# Copy_of_WX0_011_781DL.net
KiCad netlist of a schematic drawn in Altium Designer
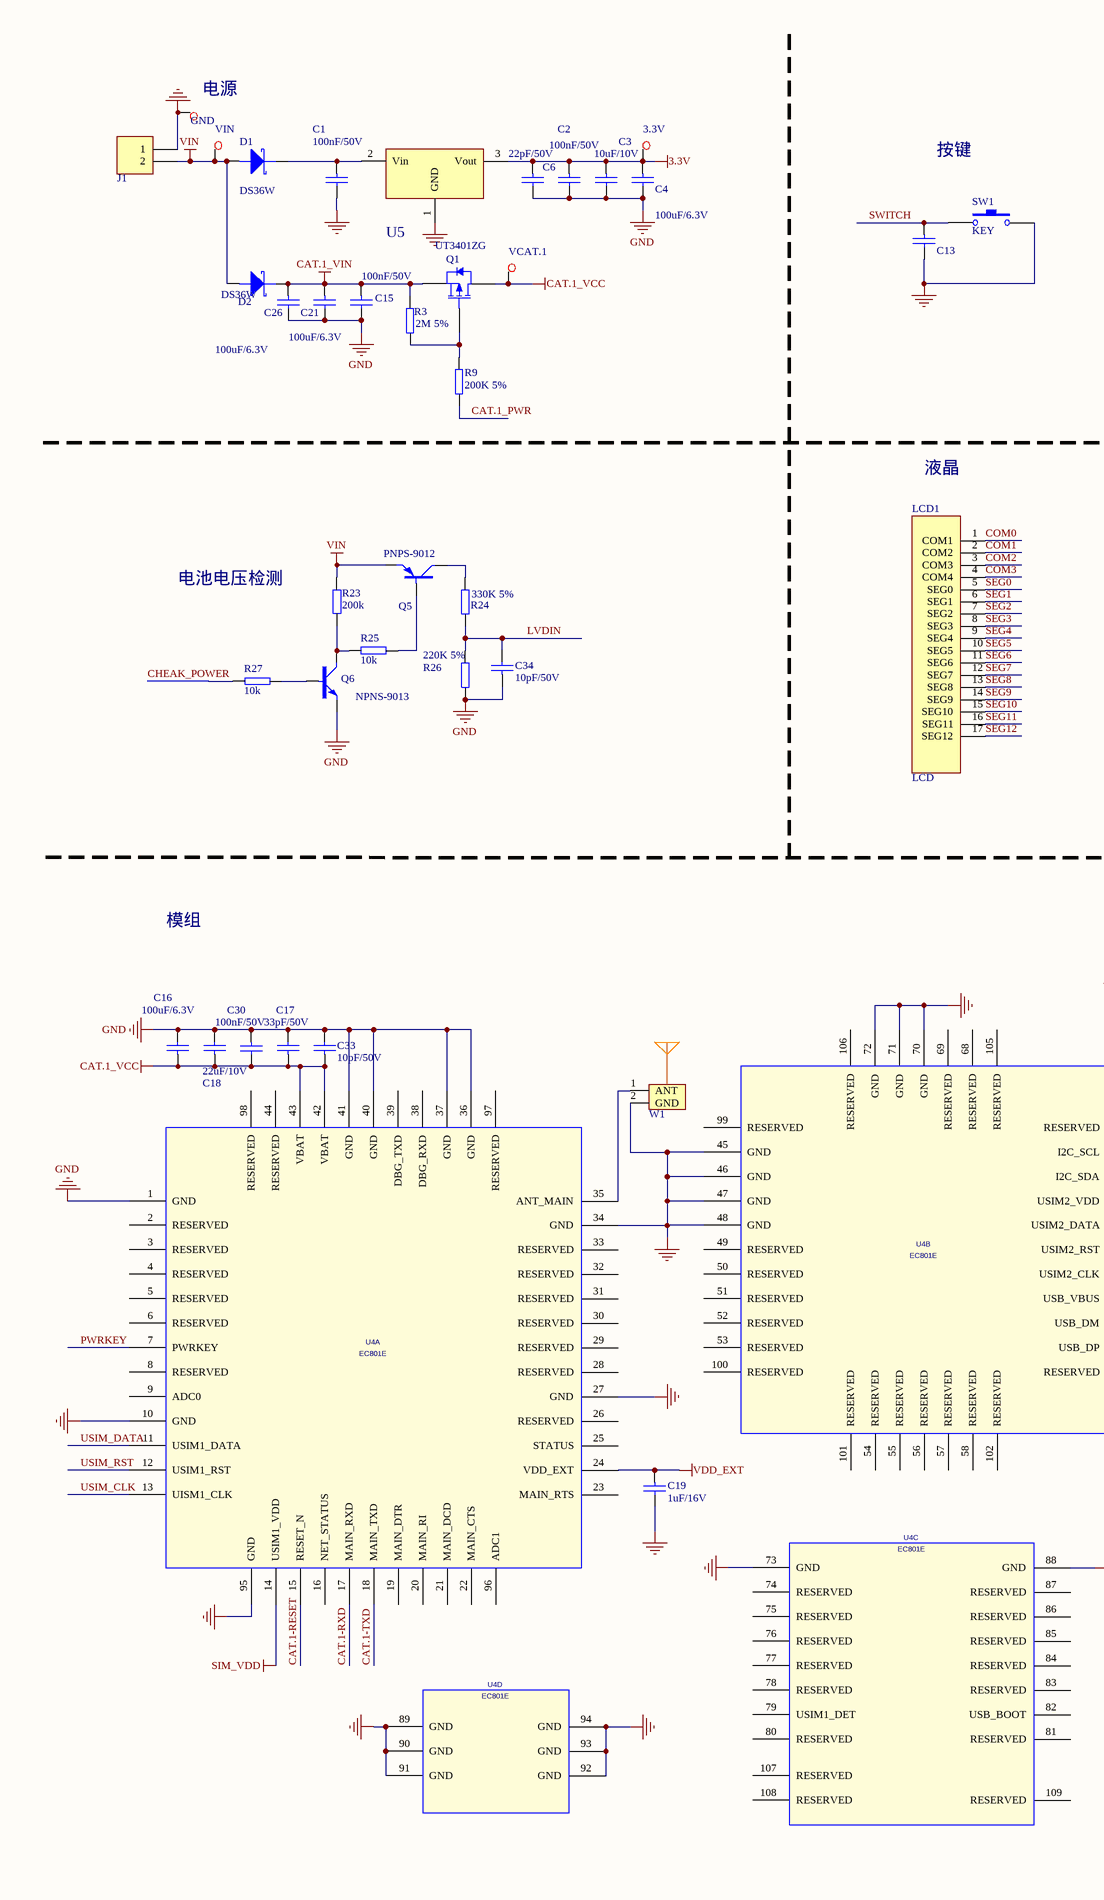
[diagram p0: Copy+of+WX0.011.781DL.schdoc, left]
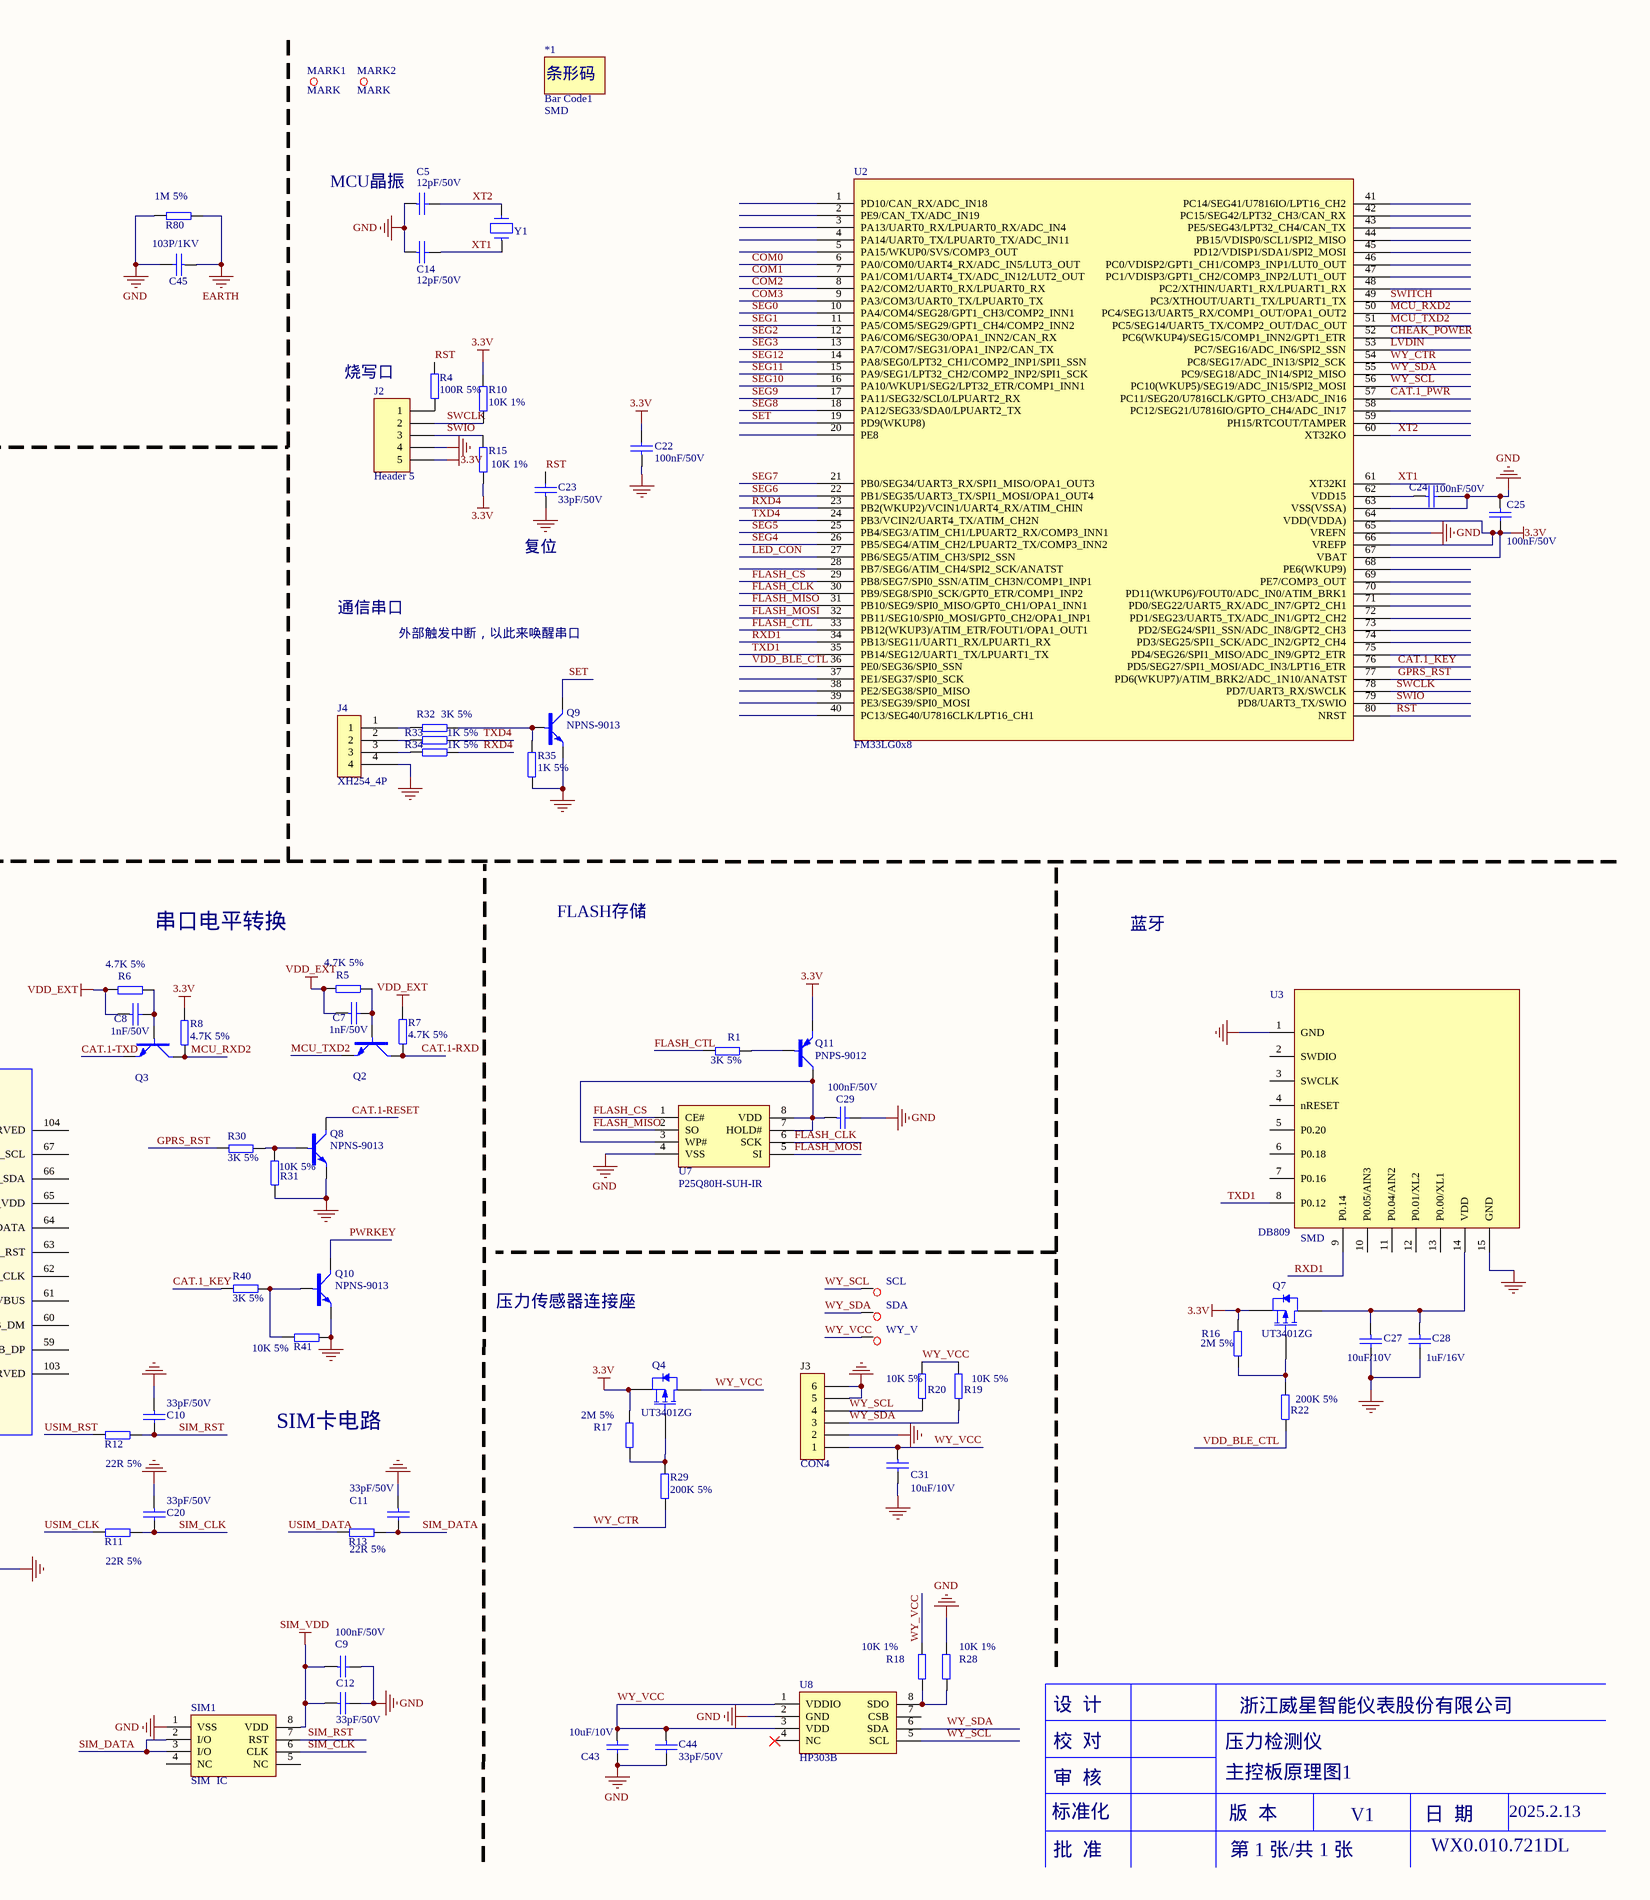
[diagram p1: Copy+of+WX0.011.781DL.schdoc, right]

(export (version "E")
  (design (tool "Eeschema 10.0.6"))
  (components
    (comp (ref "*1")
      (value "Bar Code1")
      (footprint "Bar Code1")
      (description "条形码 ,填充，无需焊接器件")
      (fields (field (name "PART NUMBER") "AD_WXHJ_Bar Code_02") (field (name "SMD/DIP") "SMD"))
      (libsource (lib "Database_Libs2") (part "05_AD_WXHJ_Bar Code_02"))
    )
    (comp (ref "3.3V")
      (value "TEST-PAD")
      (footprint "TEST-PAD")
      (description "单面焊盘测试点")
      (fields (field (name "PART NUMBER") "AD_WXHJ_TEST-PAD_01"))
      (libsource (lib "Database_Libs2") (part "TEST-PAD"))
    )
    (comp (ref "C1")
      (value "100nF/50V")
      (footprint "CAP0603")
      (description "104pF,50 V,±10%,0603,国巨,CC0603KRX7R9BB104")
      (fields (field (name "PART NUMBER") "101020103-0021"))
      (libsource (lib "Database_Libs2") (part "CC03K7R9_100N"))
    )
    (comp (ref "C2")
      (value "100nF/50V")
      (footprint "CAP0603")
      (description "104pF,50 V,±10%,0603,国巨,CC0603KRX7R9BB104")
      (fields (field (name "PART NUMBER") "101020103-0021"))
      (libsource (lib "Database_Libs2") (part "CC03K7R9_100N"))
    )
    (comp (ref "C3")
      (value "10uF/10V")
      (footprint "CAP0603")
      (description "106pF,10 V,±10%,0603,村田,GRM188R61A106KE47D")
      (fields (field (name "PART NUMBER") "101020103-0026"))
      (libsource (lib "Database_Libs2") (part "CC03K5R6_10U"))
    )
    (comp (ref "C4")
      (value "100uF/6.3V")
      (footprint "GRM1206")
      (description "100uF,6.3 V,±20%,1206,村田,GRM31CR60J107ME39L")
      (fields (field (name "PART NUMBER") "101020101-0020"))
      (libsource (lib "Database_Libs2") (part "CC06M5R5_107P"))
    )
    (comp (ref "C5")
      (value "12pF/50V")
      (footprint "CAP0603")
      (description "12P,50 V,±5%,0603,国巨,CC0603JRNPO9BN12")
      (fields (field (name "PART NUMBER") "101020103-0005"))
      (libsource (lib "Database_Libs2") (part "CC03JPO9_12P"))
    )
    (comp (ref "C6")
      (value "22pF/50V")
      (footprint "CAP0603")
      (description "22pF,50 V,±5%,0603,国巨,CC0603JRNPO9BN22")
      (fields (field (name "PART NUMBER") "101020103-0009"))
      (libsource (lib "Database_Libs2") (part "CC03JPO9_22P"))
    )
    (comp (ref "C7")
      (value "1nF/50V")
      (footprint "CAP0603")
      (description "102pF,50 V,±10%,0603,国巨,CC0603KRX7R9BB102")
      (fields (field (name "PART NUMBER") "101020103-0022"))
      (libsource (lib "Database_Libs1") (part "CC03K7R9_1N"))
    )
    (comp (ref "C8")
      (value "1nF/50V")
      (footprint "CAP0603")
      (description "102pF,50 V,±10%,0603,国巨,CC0603KRX7R9BB102")
      (fields (field (name "PART NUMBER") "101020103-0022"))
      (libsource (lib "Database_Libs1") (part "CC03K7R9_1N"))
    )
    (comp (ref "C9")
      (value "100nF/50V")
      (footprint "CAP0603")
      (description "104pF,50 V,±10%,0603,国巨,CC0603KRX7R9BB104")
      (fields (field (name "PART NUMBER") "101020103-0021"))
      (libsource (lib "Database_Libs2") (part "CC03K7R9_100N"))
    )
    (comp (ref "C10")
      (value "33pF/50V")
      (footprint "CAP0603")
      (description "33pF,50 V,±10%,0603,国巨,CC0603KRNPO9BN33")
      (fields (field (name "PART NUMBER") "101020103-0027"))
      (libsource (lib "Database_Libs2") (part "CC03KPO9_33P"))
    )
    (comp (ref "C11")
      (value "33pF/50V")
      (footprint "CAP0603")
      (description "33pF,50 V,±10%,0603,国巨,CC0603KRNPO9BN33")
      (fields (field (name "PART NUMBER") "101020103-0027"))
      (libsource (lib "Database_Libs2") (part "CC03KPO9_33P"))
    )
    (comp (ref "C12")
      (value "33pF/50V")
      (footprint "CAP0603")
      (description "33pF,50 V,±10%,0603,国巨,CC0603KRNPO9BN33")
      (fields (field (name "PART NUMBER") "101020103-0027"))
      (libsource (lib "Database_Libs2") (part "CC03KPO9_33P"))
    )
    (comp (ref "C13")
      (value "100nF/50V")
      (footprint "CAP0603")
      (description "104pF,50 V,±10%,0603,国巨,CC0603KRX7R9BB104")
      (fields (field (name "PART NUMBER") "101020103-0021"))
      (libsource (lib "Database_Libs2") (part "CC03K7R9_100N"))
    )
    (comp (ref "C14")
      (value "12pF/50V")
      (footprint "CAP0603")
      (description "12P,50 V,±5%,0603,国巨,CC0603JRNPO9BN12")
      (fields (field (name "PART NUMBER") "101020103-0005"))
      (libsource (lib "Database_Libs2") (part "CC03JPO9_12P"))
    )
    (comp (ref "C15")
      (value "100nF/50V")
      (footprint "CAP0603")
      (description "104pF,50 V,±10%,0603,国巨,CC0603KRX7R9BB104")
      (fields (field (name "PART NUMBER") "101020103-0021"))
      (libsource (lib "Database_Libs2") (part "CC03K7R9_100N"))
    )
    (comp (ref "C16")
      (value "100uF/6.3V")
      (footprint "GRM1206")
      (description "100uF,6.3 V,±20%,1206,村田,GRM31CR60J107ME39L")
      (fields (field (name "PART NUMBER") "101020101-0020"))
      (libsource (lib "Database_Libs2") (part "CC06M5R5_107P"))
    )
    (comp (ref "C17")
      (value "33pF/50V")
      (footprint "CAP0603")
      (description "33pF,50 V,±10%,0603,国巨,CC0603KRNPO9BN33")
      (fields (field (name "PART NUMBER") "101020103-0027"))
      (libsource (lib "Database_Libs2") (part "CC03KPO9_33P"))
    )
    (comp (ref "C18")
      (value "22uF/10V")
      (footprint "CAP0805")
      (description "226P,10 V,±20%,0805,村田电子有限公司,GRM21BR61A226ME51L")
      (fields (field (name "PART NUMBER") "101020102-0012"))
      (libsource (lib "Database_Libs2") (part "CC05M5R6_226P"))
    )
    (comp (ref "C19")
      (value "1uF/16V")
      (footprint "CAP0603")
      (description "105pF,16 V,±10%,0603,国巨,CC0603KRX7R7BB105")
      (fields (field (name "PART NUMBER") "101020103-0003"))
      (libsource (lib "Database_Libs1") (part "CC03K7R7_1U"))
    )
    (comp (ref "C20")
      (value "33pF/50V")
      (footprint "CAP0603")
      (description "33pF,50 V,±10%,0603,国巨,CC0603KRNPO9BN33")
      (fields (field (name "PART NUMBER") "101020103-0027"))
      (libsource (lib "Database_Libs2") (part "CC03KPO9_33P"))
    )
    (comp (ref "C21")
      (value "100uF/6.3V")
      (footprint "GRM1206")
      (description "100uF,6.3 V,±20%,1206,村田,GRM31CR60J107ME39L")
      (fields (field (name "PART NUMBER") "101020101-0020"))
      (libsource (lib "Database_Libs2") (part "CC06M5R5_107P"))
    )
    (comp (ref "C22")
      (value "100nF/50V")
      (footprint "CAP0603")
      (description "104pF,50 V,±10%,0603,国巨,CC0603KRX7R9BB104")
      (fields (field (name "PART NUMBER") "101020103-0021"))
      (libsource (lib "Database_Libs2") (part "CC03K7R9_100N"))
    )
    (comp (ref "C23")
      (value "33pF/50V")
      (footprint "CAP0603")
      (description "33pF,50 V,±10%,0603,国巨,CC0603KRNPO9BN33")
      (fields (field (name "PART NUMBER") "101020103-0027"))
      (libsource (lib "Database_Libs2") (part "CC03KPO9_33P"))
    )
    (comp (ref "C24")
      (value "100nF/50V")
      (footprint "CAP0603")
      (description "104pF,50 V,±10%,0603,国巨,CC0603KRX7R9BB104")
      (fields (field (name "PART NUMBER") "101020103-0021"))
      (libsource (lib "Database_Libs2") (part "CC03K7R9_100N"))
    )
    (comp (ref "C25")
      (value "100nF/50V")
      (footprint "CAP0603")
      (description "104pF,50 V,±10%,0603,国巨,CC0603KRX7R9BB104")
      (fields (field (name "PART NUMBER") "101020103-0021"))
      (libsource (lib "Database_Libs2") (part "CC03K7R9_100N"))
    )
    (comp (ref "C26")
      (value "100uF/6.3V")
      (footprint "GRM1206")
      (description "100uF,6.3 V,±20%,1206,村田,GRM31CR60J107ME39L")
      (fields (field (name "PART NUMBER") "101020101-0020"))
      (libsource (lib "Database_Libs2") (part "CC06M5R5_107P"))
    )
    (comp (ref "C27")
      (value "10uF/10V")
      (footprint "CAP0603")
      (description "106pF,10 V,±10%,0603,村田,GRM188R61A106KE47D")
      (fields (field (name "PART NUMBER") "101020103-0026"))
      (libsource (lib "Database_Libs2") (part "CC03K5R6_10U"))
    )
    (comp (ref "C28")
      (value "1uF/16V")
      (footprint "CAP0603")
      (description "105pF,16 V,±10%,0603,国巨,CC0603KRX7R7BB105")
      (fields (field (name "PART NUMBER") "101020103-0003"))
      (libsource (lib "Database_Libs2") (part "CC03K7R7_1U"))
    )
    (comp (ref "C29")
      (value "100nF/50V")
      (footprint "CAP0603")
      (description "104pF,50 V,±10%,0603,国巨,CC0603KRX7R9BB104")
      (fields (field (name "PART NUMBER") "101020103-0021"))
      (libsource (lib "Database_Libs2") (part "CC03K7R9_100N"))
    )
    (comp (ref "C30")
      (value "100nF/50V")
      (footprint "CAP0603")
      (description "104pF,50 V,±10%,0603,国巨,CC0603KRX7R9BB104")
      (fields (field (name "PART NUMBER") "101020103-0021"))
      (libsource (lib "Database_Libs2") (part "CC03K7R9_100N"))
    )
    (comp (ref "C31")
      (value "10uF/10V")
      (footprint "CAP0603")
      (description "106pF,10 V,±10%,0603,村田,GRM188R61A106KE47D")
      (fields (field (name "PART NUMBER") "101020103-0026"))
      (libsource (lib "Database_Libs2") (part "CC03K5R6_10U"))
    )
    (comp (ref "C33")
      (value "10pF/50V")
      (footprint "CAP0603")
      (description "10pF,50 V,±5%,0603,X7R,国巨,CC0603JRNPO9BN100")
      (fields (field (name "PART NUMBER") "101020103-0014"))
      (libsource (lib "Database_Libs2") (part "CC03JPO9_10P"))
    )
    (comp (ref "C34")
      (value "10pF/50V")
      (footprint "CAP0603")
      (description "10pF,50 V,±5%,0603,X7R,国巨,CC0603JRNPO9BN100")
      (fields (field (name "PART NUMBER") "101020103-0014"))
      (libsource (lib "Database_Libs2") (part "CC03JPO9_10P"))
    )
    (comp (ref "C43")
      (value "10uF/10V")
      (footprint "CAP0603")
      (description "106pF,10 V,±10%,0603,村田,GRM188R61A106KE47D")
      (fields (field (name "PART NUMBER") "101020103-0026"))
      (libsource (lib "Database_Libs2") (part "CC03K5R6_10U"))
    )
    (comp (ref "C44")
      (value "33pF/50V")
      (footprint "CAP0603")
      (description "33pF,50 V,±10%,0603,国巨,CC0603KRNPO9BN33")
      (fields (field (name "PART NUMBER") "101020103-0027"))
      (libsource (lib "Database_Libs2") (part "CC03KPO9_33P"))
    )
    (comp (ref "C45")
      (value "103P/1KV")
      (footprint "CAP1206")
      (description "103P/1KV,±10％,1206")
      (fields (field (name "PART NUMBER") "101020101-0003"))
      (libsource (lib "altium-import") (part "root_3_CC03K7R9_100N_"))
    )
    (comp (ref "D1")
      (value "DS36W")
      (footprint "SOD-123FL")
      (description "DS36W,SOD123-FL,3 A,42 V,60 V,浙江领晨科技有限公司,DS36W")
      (fields (field (name "PART NUMBER") "101040101-0055"))
      (libsource (lib "Database_Libs2") (part "02_DS36W"))
    )
    (comp (ref "D2")
      (value "DS36W")
      (footprint "SOD-123FL")
      (description "DS36W,SOD123-FL,3 A,42 V,60 V,浙江领晨科技有限公司,DS36W")
      (fields (field (name "PART NUMBER") "101040101-0055"))
      (libsource (lib "Database_Libs2") (part "02_DS36W"))
    )
    (comp (ref "GND")
      (value "TEST-PAD")
      (footprint "TEST-PAD")
      (description "单面焊盘测试点")
      (fields (field (name "PART NUMBER") "AD_WXHJ_TEST-PAD_01"))
      (libsource (lib "Database_Libs2") (part "TEST-PAD"))
    )
    (comp (ref "J1")
      (value "Header 2")
      (footprint "VBAT")
      (description "Header, 2-Pin")
      (libsource (lib "CBB_Lib_SCH") (part "Header 2"))
    )
    (comp (ref "J2")
      (value "Header 5")
      (footprint "PIN254_1*5SR")
      (description "Header, 5-Pin")
      (libsource (lib "CBB_Lib_SCH") (part "Header 5"))
    )
    (comp (ref "J3")
      (value "CON4")
      (footprint "WX-PH-4AB")
      (description "Connector")
      (libsource (lib "压力") (part "CON4"))
    )
    (comp (ref "J4")
      (value "XH254_4P")
      (footprint "HDR1X4_2.54")
      (description "单排插针，4PIN,间距2.54mm")
      (fields (field (name "PART NUMBER") "90003"))
      (libsource (lib "Database_Libs1") (part "XH254_4P"))
    )
    (comp (ref "LCD1") (value "LCD") (footprint "JR-H25903AFP") (libsource (lib "压力检测仪") (part "LCDSH")))
    (comp (ref "MARK1")
      (value "MARK")
      (footprint "MARK")
      (description "MARK点")
      (fields (field (name "PART NUMBER") "AD_WXHJ_MARK_01"))
      (libsource (lib "Database_Libs2") (part "MARK"))
    )
    (comp (ref "MARK2")
      (value "MARK")
      (footprint "MARK")
      (description "MARK点")
      (fields (field (name "PART NUMBER") "AD_WXHJ_MARK_01"))
      (libsource (lib "Database_Libs2") (part "MARK"))
    )
    (comp (ref "Q1")
      (value "UT3401ZG")
      (footprint "SOT-23")
      (description "UT3401ZG,P-MOS,SOT-23,UTC,UT3401ZG")
      (fields (field (name "PART NUMBER") "101040201-0013"))
      (libsource (lib "Database_Libs2") (part "03_P-UT3401ZG"))
    )
    (comp (ref "Q2")
      (value "NPNS-9013")
      (footprint "SOT-23")
      (description "9013,NPN,SOT-23,长电,S9013")
      (fields (field (name "PART NUMBER") "101040201-0002"))
      (libsource (lib "Database_Libs2") (part "03_NPNS-9013"))
    )
    (comp (ref "Q3")
      (value "NPNS-9013")
      (footprint "SOT-23")
      (description "9013,NPN,SOT-23,长电,S9013")
      (fields (field (name "PART NUMBER") "101040201-0002"))
      (libsource (lib "Database_Libs2") (part "03_NPNS-9013"))
    )
    (comp (ref "Q4")
      (value "UT3401ZG")
      (footprint "SOT-23")
      (description "UT3401ZG,P-MOS,SOT-23,UTC,UT3401ZG")
      (fields (field (name "PART NUMBER") "101040201-0013"))
      (libsource (lib "Database_Libs2") (part "03_P-UT3401ZG"))
    )
    (comp (ref "Q5")
      (value "PNPS-9012")
      (footprint "SOT-23")
      (description "9012,PNP,SOT-23,JCET;长电,S9012")
      (fields (field (name "PART NUMBER") "101040201-0001"))
      (libsource (lib "Database_Libs2") (part "03_PNPS-9012"))
    )
    (comp (ref "Q6")
      (value "NPNS-9013")
      (footprint "SOT-23")
      (description "9013,NPN,SOT-23,长电,S9013")
      (fields (field (name "PART NUMBER") "101040201-0002"))
      (libsource (lib "Database_Libs2") (part "03_NPNS-9013"))
    )
    (comp (ref "Q7")
      (value "UT3401ZG")
      (footprint "SOT-23")
      (description "UT3401ZG,P-MOS,SOT-23,UTC,UT3401ZG")
      (fields (field (name "PART NUMBER") "101040201-0013"))
      (libsource (lib "Database_Libs2") (part "03_P-UT3401ZG"))
    )
    (comp (ref "Q8")
      (value "NPNS-9013")
      (footprint "SOT-23")
      (description "9013,NPN,SOT-23,长电,S9013")
      (fields (field (name "PART NUMBER") "101040201-0002"))
      (libsource (lib "Database_Libs2") (part "03_NPNS-9013"))
    )
    (comp (ref "Q9")
      (value "NPNS-9013")
      (footprint "SOT-23")
      (description "9013,NPN,SOT-23,长电,S9013")
      (fields (field (name "PART NUMBER") "101040201-0002"))
      (libsource (lib "Database_Libs2") (part "03_NPNS-9013"))
    )
    (comp (ref "Q10")
      (value "NPNS-9013")
      (footprint "SOT-23")
      (description "9013,NPN,SOT-23,长电,S9013")
      (fields (field (name "PART NUMBER") "101040201-0002"))
      (libsource (lib "Database_Libs1") (part "03_NPNS-9013"))
    )
    (comp (ref "Q11")
      (value "PNPS-9012")
      (footprint "SOT-23")
      (description "9012,PNP,SOT-23,JCET;长电,S9012")
      (fields (field (name "PART NUMBER") "101040201-0001"))
      (libsource (lib "Database_Libs2") (part "03_PNPS-9012"))
    )
    (comp (ref "R1")
      (value "3K 5%")
      (footprint "RES0603")
      (description "国巨,±5%,0603,,155 ℃,-55 ℃,RC0603JR-073KL,无铅,100 ppm/℃,1/10W,,3K")
      (fields (field (name "PART NUMBER") "101010103-0006"))
      (libsource (lib "Database_Libs2") (part "RC03J_3K"))
    )
    (comp (ref "R3")
      (value "2M 5%")
      (footprint "RES0603")
      (description "国巨,±5%,0603,,155 ℃,-55 ℃,RC0603JR-072ML,含铅,100 ppm/℃,1/10W,,2M")
      (fields (field (name "PART NUMBER") "101010103-0025"))
      (libsource (lib "Database_Libs2") (part "RC03J_2M"))
    )
    (comp (ref "R4")
      (value "100R 5%")
      (footprint "RES0603")
      (description "100R,±5%,1/10W,0603,国巨,RC0603JR-07100RL")
      (fields (field (name "PART NUMBER") "101010103-0022"))
      (libsource (lib "Database_Libs2") (part "RC03J_100R"))
    )
    (comp (ref "R5")
      (value "4.7K 5%")
      (footprint "RES0603")
      (description "4.7K±5%,1/10W,0603")
      (fields (field (name "PART NUMBER") "101010103-0042"))
      (libsource (lib "Database_Libs2") (part "RC03J_4.7K"))
    )
    (comp (ref "R6")
      (value "4.7K 5%")
      (footprint "RES0603")
      (description "4.7K±5%,1/10W,0603")
      (fields (field (name "PART NUMBER") "101010103-0042"))
      (libsource (lib "Database_Libs2") (part "RC03J_4.7K"))
    )
    (comp (ref "R7")
      (value "4.7K 5%")
      (footprint "RES0603")
      (description "4.7K±5%,1/10W,0603")
      (fields (field (name "PART NUMBER") "101010103-0042"))
      (libsource (lib "Database_Libs2") (part "RC03J_4.7K"))
    )
    (comp (ref "R8")
      (value "4.7K 5%")
      (footprint "RES0603")
      (description "4.7K±5%,1/10W,0603")
      (fields (field (name "PART NUMBER") "101010103-0042"))
      (libsource (lib "Database_Libs2") (part "RC03J_4.7K"))
    )
    (comp (ref "R9")
      (value "200K 5%")
      (footprint "RES0603")
      (description "200K,±5%,1/10W,0603,国巨,RC0603JR-07200KL")
      (fields (field (name "PART NUMBER") "101010103-0034"))
      (libsource (lib "Database_Libs2") (part "RC03J_200K"))
    )
    (comp (ref "R10")
      (value "10K 1%")
      (footprint "RES0603")
      (description "10K±1%,1/10W,0603")
      (fields (field (name "PART NUMBER") "101010103-0052"))
      (libsource (lib "Database_Libs2") (part "RC03J_10K"))
    )
    (comp (ref "R11")
      (value "22R 5%")
      (footprint "RES0603")
      (description "国巨,±5%,0603,,155 ℃,-55 ℃,RC0603JR-0722RL,无铅,200 ppm/℃,1/10W,,22欧")
      (fields (field (name "PART NUMBER") "101010103-0009"))
      (libsource (lib "Database_Libs2") (part "RC03J_22R"))
    )
    (comp (ref "R12")
      (value "22R 5%")
      (footprint "RES0603")
      (description "国巨,±5%,0603,,155 ℃,-55 ℃,RC0603JR-0722RL,无铅,200 ppm/℃,1/10W,,22欧")
      (fields (field (name "PART NUMBER") "101010103-0009"))
      (libsource (lib "Database_Libs2") (part "RC03J_22R"))
    )
    (comp (ref "R13")
      (value "22R 5%")
      (footprint "RES0603")
      (description "国巨,±5%,0603,,155 ℃,-55 ℃,RC0603JR-0722RL,无铅,200 ppm/℃,1/10W,,22欧")
      (fields (field (name "PART NUMBER") "101010103-0009"))
      (libsource (lib "Database_Libs2") (part "RC03J_22R"))
    )
    (comp (ref "R15")
      (value "10K 1%")
      (footprint "RES0603")
      (description "10K±1%,1/10W,0603")
      (fields (field (name "PART NUMBER") "101010103-0052"))
      (libsource (lib "Database_Libs2") (part "RC03J_10K"))
    )
    (comp (ref "R16")
      (value "2M 5%")
      (footprint "RES0603")
      (description "国巨,±5%,0603,,155 ℃,-55 ℃,RC0603JR-072ML,含铅,100 ppm/℃,1/10W,,2M")
      (fields (field (name "PART NUMBER") "101010103-0025"))
      (libsource (lib "Database_Libs2") (part "RC03J_2M"))
    )
    (comp (ref "R17")
      (value "2M 5%")
      (footprint "RES0603")
      (description "国巨,±5%,0603,,155 ℃,-55 ℃,RC0603JR-072ML,含铅,100 ppm/℃,1/10W,,2M")
      (fields (field (name "PART NUMBER") "101010103-0025"))
      (libsource (lib "Database_Libs2") (part "RC03J_2M"))
    )
    (comp (ref "R18")
      (value "10K 1%")
      (footprint "RES0603")
      (description "10K±1%,1/10W,0603")
      (fields (field (name "PART NUMBER") "101010103-0052"))
      (libsource (lib "Database_Libs2") (part "RC03J_10K"))
    )
    (comp (ref "R19")
      (value "10K 5%")
      (footprint "RES0603")
      (description "国巨,±5%,0603,,155 ℃,-55 ℃,RC0603JR-0710KL,无铅,200 ppm/℃,1/10W,,10K")
      (fields (field (name "PART NUMBER") "101010103-0003"))
      (libsource (lib "Database_Libs2") (part "RC03J_10K"))
    )
    (comp (ref "R20")
      (value "10K 5%")
      (footprint "RES0603")
      (description "国巨,±5%,0603,,155 ℃,-55 ℃,RC0603JR-0710KL,无铅,200 ppm/℃,1/10W,,10K")
      (fields (field (name "PART NUMBER") "101010103-0003"))
      (libsource (lib "Database_Libs2") (part "RC03J_10K"))
    )
    (comp (ref "R22")
      (value "200K 5%")
      (footprint "RES0603")
      (description "200K,±5%,1/10W,0603,国巨,RC0603JR-07200KL")
      (fields (field (name "PART NUMBER") "101010103-0034"))
      (libsource (lib "Database_Libs2") (part "RC03J_200K"))
    )
    (comp (ref "R23") (value "200k") (footprint "RES0603") (libsource (lib "CBB_Lib_SCH") (part "RES")))
    (comp (ref "R24")
      (value "330K 5%")
      (footprint "RES0603")
      (description "330K,±5%,1/10W,0603,国巨,RC0603JR-07330KL")
      (fields (field (name "PART NUMBER") "101010103-0066"))
      (libsource (lib "Database_Libs2") (part "RC03J_330K"))
    )
    (comp (ref "R25") (value "10k") (footprint "RES0603") (libsource (lib "CBB_Lib_SCH") (part "RES")))
    (comp (ref "R26")
      (value "220K 5%")
      (footprint "RES0603")
      (description "220K,±5%,1/10W,0603,国巨,RC0603JR-07220KL")
      (fields (field (name "PART NUMBER") "101010103-0044"))
      (libsource (lib "Database_Libs2") (part "RC03J_220K"))
    )
    (comp (ref "R27") (value "10k") (footprint "RES0603") (libsource (lib "CBB_Lib_SCH") (part "RES")))
    (comp (ref "R28")
      (value "10K 1%")
      (footprint "RES0603")
      (description "10K±1%,1/10W,0603")
      (fields (field (name "PART NUMBER") "101010103-0052"))
      (libsource (lib "Database_Libs2") (part "RC03J_10K"))
    )
    (comp (ref "R29")
      (value "200K 5%")
      (footprint "RES0603")
      (description "10K±5%,1/10W,0603")
      (fields (field (name "PART NUMBER") "101010103-0003"))
      (libsource (lib "Database_Libs1") (part "RC03JF_10K"))
    )
    (comp (ref "R30")
      (value "3K 5%")
      (footprint "RES0603")
      (description "国巨,±5%,0603,,155 ℃,-55 ℃,RC0603JR-073KL,无铅,100 ppm/℃,1/10W,,3K")
      (fields (field (name "PART NUMBER") "101010103-0006"))
      (libsource (lib "Database_Libs2") (part "RC03J_3K"))
    )
    (comp (ref "R31")
      (value "10K 5%")
      (footprint "RES0603")
      (description "国巨,±5%,0603,,155 ℃,-55 ℃,RC0603JR-0710KL,无铅,200 ppm/℃,1/10W,,10K")
      (fields (field (name "PART NUMBER") "101010103-0003"))
      (libsource (lib "Database_Libs2") (part "RC03J_10K"))
    )
    (comp (ref "R32")
      (value "3K 5%")
      (footprint "RES0603")
      (description "3K±5%,1/10W,0603")
      (fields (field (name "PART NUMBER") "101010103-0006"))
      (libsource (lib "Database_Libs1") (part "RC03JF_3K"))
    )
    (comp (ref "R33")
      (value "1K 5%")
      (footprint "RES0603")
      (description "3K±5%,1/10W,0603")
      (fields (field (name "PART NUMBER") "101010103-0006"))
      (libsource (lib "Database_Libs1") (part "RC03JF_3K"))
    )
    (comp (ref "R34")
      (value "1K 5%")
      (footprint "RES0603")
      (description "3K±5%,1/10W,0603")
      (fields (field (name "PART NUMBER") "101010103-0006"))
      (libsource (lib "Database_Libs1") (part "RC03JF_3K"))
    )
    (comp (ref "R35")
      (value "1K 5%")
      (footprint "RES0603")
      (description "20K±5%,1/10W,0603")
      (fields (field (name "PART NUMBER") "101010103-0004"))
      (libsource (lib "Database_Libs1") (part "RC03JF_20K"))
    )
    (comp (ref "R40")
      (value "3K 5%")
      (footprint "RES0603")
      (description "3K±5%,1/10W,0603")
      (fields (field (name "PART NUMBER") "101010103-0006"))
      (libsource (lib "Database_Libs1") (part "RC03JF_3K"))
    )
    (comp (ref "R41")
      (value "10K 5%")
      (footprint "RES0603")
      (description "国巨,±5%,0603,,155 ℃,-55 ℃,RC0603JR-0710KL,无铅,200 ppm/℃,1/10W,,10K")
      (fields (field (name "PART NUMBER") "101010103-0003"))
      (libsource (lib "Database_Libs2") (part "RC03J_10K"))
    )
    (comp (ref "R80")
      (value "1M 5%")
      (footprint "RES1206")
      (description "国巨,±5%,0603,,155 ℃,-55 ℃,RC0603JR-071ML,无铅,200 ppm/℃,1/10W,,1M")
      (fields (field (name "PART NUMBER") "101010103-0002"))
      (libsource (lib "Database_Libs2") (part "RC03J_1M"))
    )
    (comp (ref "SCL")
      (value "TEST-PAD")
      (footprint "TEST-PAD")
      (description "单面焊盘测试点")
      (fields (field (name "PART NUMBER") "AD_WXHJ_TEST-PAD_01"))
      (libsource (lib "Database_Libs2") (part "TEST-PAD"))
    )
    (comp (ref "SDA")
      (value "TEST-PAD")
      (footprint "TEST-PAD")
      (description "单面焊盘测试点")
      (fields (field (name "PART NUMBER") "AD_WXHJ_TEST-PAD_01"))
      (libsource (lib "Database_Libs2") (part "TEST-PAD"))
    )
    (comp (ref "SIM1")
      (value "SIM  IC")
      (footprint "SIMIC")
      (libsource (lib "PCB_Project") (part "SIMCARD_1"))
    )
    (comp (ref "SW1")
      (value "KEY")
      (footprint "DIP-6X6X8")
      (description "Switch")
      (libsource (lib "Free Documents") (part "SW-PB"))
    )
    (comp (ref "U2") (value "FM33LG0x8") (footprint "LQFP80") (libsource (lib "FM_MCU") (part "FM33LG0x8")))
    (comp (ref "U3")
      (value "DB809")
      (footprint "DB809")
      (description "北高智蓝牙模块DB809")
      (fields (field (name "PART NUMBER") "1011402-0194") (field (name "SMD/DIP") "SMD"))
      (libsource (lib "Database_Libs2") (part "01_DB809"))
    )
    (comp (ref "U4")
      (value "EC801E")
      (footprint "EC801E")
      (description "EC801E Moudle 109PIN 17.7X15.8mm H2.4mm RO")
      (fields (field (name "MANUFACTURER") "QUECTEL"))
      (libsource (lib "未添加") (part "EC801E"))
    )
    (comp (ref "U5")
      (value "CE6232A33P")
      (footprint "SOT-89")
      (description "CE6232-3.3,CE6232-3.3,SOT89-3,8V,1.8V,0.11V,3.3V,300mA,0.8uA,南京芯力微电子有限公司")
      (fields (field (name "PART NUMBER") "1010503-0029"))
      (libsource (lib "Database_Libs2") (part "02_CE6232A33P"))
    )
    (comp (ref "U7")
      (value "P25Q80H-SUH-IR")
      (footprint "SOP-8L-200MIL")
      (description "P25Q80H-SUH-IR,SOP8208mil,普冉半导体（上海）股份有限公司,P25Q80H-SUH-IR")
      (fields (field (name "PART NUMBER") "101050101-0218"))
      (libsource (lib "Database_Libs2") (part "04_P25Q80H-SUH-IR"))
    )
    (comp (ref "U8") (value "HP303B") (footprint "LGA_8") (libsource (lib "Schlib2") (part "HP303B")))
    (comp (ref "VCAT.1")
      (value "TEST-PAD")
      (footprint "TEST-PAD")
      (description "单面焊盘测试点")
      (fields (field (name "PART NUMBER") "AD_WXHJ_TEST-PAD_01"))
      (libsource (lib "Database_Libs2") (part "TEST-PAD"))
    )
    (comp (ref "VIN")
      (value "TEST-PAD")
      (footprint "TEST-PAD")
      (description "单面焊盘测试点")
      (fields (field (name "PART NUMBER") "AD_WXHJ_TEST-PAD_01"))
      (libsource (lib "Database_Libs2") (part "TEST-PAD"))
    )
    (comp (ref "W1")
      (value "天线")
      (footprint "ANT-IPEX_1")
      (description "UB06000058A,3*3.1*1.25mm,公头,单排,IPEX一代板端")
      (fields (field (name "PART NUMBER") "1010902-0145"))
      (libsource (lib "Database_Libs2") (part "天线"))
    )
    (comp (ref "WY_V")
      (value "TEST-PAD")
      (footprint "TEST-PAD")
      (description "单面焊盘测试点")
      (fields (field (name "PART NUMBER") "AD_WXHJ_TEST-PAD_01"))
      (libsource (lib "Database_Libs2") (part "TEST-PAD"))
    )
    (comp (ref "Y1")
      (value "SF32WK32768D71T005")
      (footprint "SMD-3215_2P")
      (description "SF32WK32768D71T005,3215,32.768kHz,-0.03 ppm/℃,无源,湖北泰晶电子科技股份有限公司,SF32WK32768D71T005")
      (fields (field (name "PART NUMBER") "1010601-0020"))
      (libsource (lib "Database_Libs2") (part "04_XTALSG7QD_32.768kD"))
    )
  )
  (nets
    (net (code "1") (name "/CAT.1-RESET") (class "Default")
      (node (ref "Q8") (pin "3") (pinfunction "C_3") (pintype "passive"))
      (node (ref "U4") (pin "15") (pinfunction "RESET_N_15") (pintype "passive"))
    )
    (net (code "2") (name "/CAT.1-RXD") (class "Default")
      (node (ref "Q2") (pin "3") (pinfunction "C_3") (pintype "passive"))
      (node (ref "R7") (pin "1") (pinfunction "1_1") (pintype "passive"))
      (node (ref "U4") (pin "17") (pinfunction "MAIN_RXD_17") (pintype "passive"))
    )
    (net (code "3") (name "/CAT.1-TXD") (class "Default")
      (node (ref "Q3") (pin "2") (pinfunction "E_2") (pintype "passive"))
      (node (ref "U4") (pin "18") (pinfunction "MAIN_TXD_18") (pintype "passive"))
    )
    (net (code "4") (name "/CAT.1_KEY") (class "Default")
      (node (ref "R40") (pin "1") (pinfunction "1_1") (pintype "passive"))
      (node (ref "U2") (pin "76") (pinfunction "PD5/SEG27/SPI1_MOSI/ADC_IN3/LPT16_ETR_76") (pintype "passive"))
    )
    (net (code "5") (name "/CAT.1_PWR") (class "Default")
      (node (ref "R9") (pin "1") (pinfunction "1_1") (pintype "passive"))
      (node (ref "U2") (pin "57") (pinfunction "PC11/SEG20/U7816CLK/GPTO_CH3/ADC_IN16_57") (pintype "passive"))
    )
    (net (code "6") (name "/CHEAK_POWER") (class "Default")
      (node (ref "R27") (pin "1") (pintype "passive"))
      (node (ref "U2") (pin "52") (pinfunction "PC6(WKUP4)/SEG15/COMP1_INN2/GPT1_ETR_52") (pintype "passive"))
    )
    (net (code "7") (name "/COM0") (class "Default")
      (node (ref "LCD1") (pin "1") (pinfunction "COM1_1") (pintype "passive"))
      (node (ref "U2") (pin "6") (pinfunction "PA0/COM0/UART4_RX/ADC_IN5/LUT3_OUT_6") (pintype "passive"))
    )
    (net (code "8") (name "/COM1") (class "Default")
      (node (ref "LCD1") (pin "2") (pinfunction "COM2_2") (pintype "passive"))
      (node (ref "U2") (pin "7") (pinfunction "PA1/COM1/UART4_TX/ADC_IN12/LUT2_OUT_7") (pintype "passive"))
    )
    (net (code "9") (name "/COM2") (class "Default")
      (node (ref "LCD1") (pin "3") (pinfunction "COM3_3") (pintype "passive"))
      (node (ref "U2") (pin "8") (pinfunction "PA2/COM2/UART0_RX/LPUART0_RX_8") (pintype "passive"))
    )
    (net (code "10") (name "/COM3") (class "Default")
      (node (ref "LCD1") (pin "4") (pinfunction "COM4_4") (pintype "passive"))
      (node (ref "U2") (pin "9") (pinfunction "PA3/COM3/UART0_TX/LPUART0_TX_9") (pintype "passive"))
    )
    (net (code "11") (name "/FLASH_CLK") (class "Default")
      (node (ref "U2") (pin "30") (pinfunction "PB9/SEG8/SPI0_SCK/GPT0_ETR/COMP1_INP2_30") (pintype "passive"))
      (node (ref "U7") (pin "6") (pinfunction "SCK_6") (pintype "passive"))
    )
    (net (code "12") (name "/FLASH_CS") (class "Default")
      (node (ref "U2") (pin "29") (pinfunction "PB8/SEG7/SPI0_SSN/ATIM_CH3N/COMP1_INP1_29") (pintype "passive"))
      (node (ref "U7") (pin "1") (pinfunction "CE#_1") (pintype "passive"))
    )
    (net (code "13") (name "/FLASH_CTL") (class "Default")
      (node (ref "R1") (pin "1") (pinfunction "1_1") (pintype "passive"))
      (node (ref "U2") (pin "33") (pinfunction "PB12(WKUP3)/ATIM_ETR/FOUT1/OPA1_OUT1_33") (pintype "passive"))
    )
    (net (code "14") (name "/FLASH_MISO") (class "Default")
      (node (ref "U2") (pin "31") (pinfunction "PB10/SEG9/SPI0_MISO/GPT0_CH1/OPA1_INN1_31") (pintype "passive"))
      (node (ref "U7") (pin "2") (pinfunction "SO_2") (pintype "passive"))
    )
    (net (code "15") (name "/FLASH_MOSI") (class "Default")
      (node (ref "U2") (pin "32") (pinfunction "PB11/SEG10/SPI0_MOSI/GPT0_CH2/OPA1_INP1_32") (pintype "passive"))
      (node (ref "U7") (pin "5") (pinfunction "SI_5") (pintype "passive"))
    )
    (net (code "16") (name "/GPRS_RST") (class "Default")
      (node (ref "R30") (pin "1") (pinfunction "1_1") (pintype "passive"))
      (node (ref "U2") (pin "77") (pinfunction "PD6(WKUP7)/ATIM_BRK2/ADC_1N10/ANATST_77") (pintype "passive"))
    )
    (net (code "17") (name "/LED_CON") (class "Default")
      (node (ref "U2") (pin "27") (pinfunction "PB6/SEG5/ATIM_CH3/SPI2_SSN_27") (pintype "passive"))
    )
    (net (code "18") (name "/LVDIN") (class "Default")
      (node (ref "C34") (pin "2") (pinfunction "2_2") (pintype "passive"))
      (node (ref "R24") (pin "1") (pinfunction "1_1") (pintype "passive"))
      (node (ref "R26") (pin "2") (pinfunction "2_2") (pintype "passive"))
      (node (ref "U2") (pin "53") (pinfunction "PC7/SEG16/ADC_IN6/SPI2_SSN_53") (pintype "passive"))
    )
    (net (code "19") (name "/MCU_RXD2") (class "Default")
      (node (ref "Q3") (pin "3") (pinfunction "C_3") (pintype "passive"))
      (node (ref "R8") (pin "1") (pinfunction "1_1") (pintype "passive"))
      (node (ref "U2") (pin "50") (pinfunction "PC4/SEG13/UART5_RX/COMP1_OUT/OPA1_OUT2_50") (pintype "passive"))
    )
    (net (code "20") (name "/MCU_TXD2") (class "Default")
      (node (ref "Q2") (pin "2") (pinfunction "E_2") (pintype "passive"))
      (node (ref "U2") (pin "51") (pinfunction "PC5/SEG14/UART5_TX/COMP2_OUT/DAC_OUT_51") (pintype "passive"))
    )
    (net (code "21") (name "/PWRKEY") (class "Default")
      (node (ref "Q10") (pin "3") (pinfunction "C_3") (pintype "passive"))
      (node (ref "U4") (pin "7") (pinfunction "PWRKEY_7") (pintype "passive"))
    )
    (net (code "22") (name "/RST") (class "Default")
      (node (ref "C23") (pin "2") (pinfunction "2_2") (pintype "passive"))
      (node (ref "R4") (pin "1") (pinfunction "1_1") (pintype "passive"))
      (node (ref "U2") (pin "80") (pinfunction "NRST_80") (pintype "passive"))
    )
    (net (code "23") (name "/RXD1") (class "Default")
      (node (ref "U2") (pin "34") (pinfunction "PB13/SEG11/UART1_RX/LPUART1_RX_34") (pintype "passive"))
      (node (ref "U3") (pin "9") (pinfunction "P0.14_9") (pintype "passive"))
    )
    (net (code "24") (name "/RXD4") (class "Default")
      (node (ref "R34") (pin "2") (pinfunction "2_2") (pintype "passive"))
      (node (ref "U2") (pin "23") (pinfunction "PB2(WKUP2)/VCIN1/UART4_RX/ATIM_CHIN_23") (pintype "passive"))
    )
    (net (code "25") (name "/SEG0") (class "Default")
      (node (ref "LCD1") (pin "5") (pinfunction "SEG0_5") (pintype "passive"))
      (node (ref "U2") (pin "10") (pinfunction "PA4/COM4/SEG28/GPT1_CH3/COMP2_INN1_10") (pintype "passive"))
    )
    (net (code "26") (name "/SEG1") (class "Default")
      (node (ref "LCD1") (pin "6") (pinfunction "SEG1_6") (pintype "passive"))
      (node (ref "U2") (pin "11") (pinfunction "PA5/COM5/SEG29/GPT1_CH4/COMP2_INN2_11") (pintype "passive"))
    )
    (net (code "27") (name "/SEG2") (class "Default")
      (node (ref "LCD1") (pin "7") (pinfunction "SEG2_7") (pintype "passive"))
      (node (ref "U2") (pin "12") (pinfunction "PA6/COM6/SEG30/OPA1_INN2/CAN_RX_12") (pintype "passive"))
    )
    (net (code "28") (name "/SEG3") (class "Default")
      (node (ref "LCD1") (pin "8") (pinfunction "SEG3_8") (pintype "passive"))
      (node (ref "U2") (pin "13") (pinfunction "PA7/COM7/SEG31/OPA1_INP2/CAN_TX_13") (pintype "passive"))
    )
    (net (code "29") (name "/SEG4") (class "Default")
      (node (ref "LCD1") (pin "9") (pinfunction "SEG4_9") (pintype "passive"))
      (node (ref "U2") (pin "26") (pinfunction "PB5/SEG4/ATIM_CH2/LPUART2_TX/COMP3_INN2_26") (pintype "passive"))
    )
    (net (code "30") (name "/SEG5") (class "Default")
      (node (ref "LCD1") (pin "10") (pinfunction "SEG5_10") (pintype "passive"))
      (node (ref "U2") (pin "25") (pinfunction "PB4/SEG3/ATIM_CH1/LPUART2_RX/COMP3_INN1_25") (pintype "passive"))
    )
    (net (code "31") (name "/SEG6") (class "Default")
      (node (ref "LCD1") (pin "11") (pinfunction "SEG6_11") (pintype "passive"))
      (node (ref "U2") (pin "22") (pinfunction "PB1/SEG35/UART3_TX/SPI1_MOSI/OPA1_OUT4_22") (pintype "passive"))
    )
    (net (code "32") (name "/SEG7") (class "Default")
      (node (ref "LCD1") (pin "12") (pinfunction "SEG7_12") (pintype "passive"))
      (node (ref "U2") (pin "21") (pinfunction "PB0/SEG34/UART3_RX/SPI1_MISO/OPA1_OUT3_21") (pintype "passive"))
    )
    (net (code "33") (name "/SEG8") (class "Default")
      (node (ref "LCD1") (pin "13") (pinfunction "SEG8_13") (pintype "passive"))
      (node (ref "U2") (pin "18") (pinfunction "PA12/SEG33/SDA0/LPUART2_TX_18") (pintype "passive"))
    )
    (net (code "34") (name "/SEG9") (class "Default")
      (node (ref "LCD1") (pin "14") (pinfunction "SEG9_14") (pintype "passive"))
      (node (ref "U2") (pin "17") (pinfunction "PA11/SEG32/SCL0/LPUART2_RX_17") (pintype "passive"))
    )
    (net (code "35") (name "/SEG10") (class "Default")
      (node (ref "LCD1") (pin "15") (pinfunction "SEG10_15") (pintype "passive"))
      (node (ref "U2") (pin "16") (pinfunction "PA10/WKUP1/SEG2/LPT32_ETR/COMP1_INN1_16") (pintype "passive"))
    )
    (net (code "36") (name "/SEG11") (class "Default")
      (node (ref "LCD1") (pin "16") (pinfunction "SEG11_16") (pintype "passive"))
      (node (ref "U2") (pin "15") (pinfunction "PA9/SEG1/LPT32_CH2/COMP2_INP2/SPI1_SCK_15") (pintype "passive"))
    )
    (net (code "37") (name "/SEG12") (class "Default")
      (node (ref "LCD1") (pin "17") (pinfunction "SEG12_17") (pintype "passive"))
      (node (ref "U2") (pin "14") (pinfunction "PA8/SEG0/LPT32_CH1/COMP2_INP1/SPI1_SSN_14") (pintype "passive"))
    )
    (net (code "38") (name "/SET") (class "Default")
      (node (ref "Q9") (pin "3") (pinfunction "C_3") (pintype "passive"))
      (node (ref "U2") (pin "19") (pinfunction "PD9(WKUP8)_19") (pintype "passive"))
    )
    (net (code "39") (name "/SIM_CLK") (class "Default")
      (node (ref "C20") (pin "2") (pinfunction "2_2") (pintype "passive"))
      (node (ref "R11") (pin "2") (pinfunction "2_2") (pintype "passive"))
      (node (ref "SIM1") (pin "6") (pinfunction "CLK_6") (pintype "passive"))
    )
    (net (code "40") (name "/SIM_DATA") (class "Default")
      (node (ref "C11") (pin "2") (pinfunction "2_2") (pintype "passive"))
      (node (ref "R13") (pin "2") (pinfunction "2_2") (pintype "passive"))
      (node (ref "SIM1") (pin "2") (pinfunction "I/O_2") (pintype "passive"))
      (node (ref "SIM1") (pin "3") (pinfunction "I/O_3") (pintype "passive"))
    )
    (net (code "41") (name "/SIM_RST") (class "Default")
      (node (ref "C10") (pin "2") (pinfunction "2_2") (pintype "passive"))
      (node (ref "R12") (pin "2") (pinfunction "2_2") (pintype "passive"))
      (node (ref "SIM1") (pin "7") (pinfunction "RST_7") (pintype "passive"))
    )
    (net (code "42") (name "/SWCLK") (class "Default")
      (node (ref "J2") (pin "2") (pinfunction "2_2") (pintype "passive"))
      (node (ref "R10") (pin "1") (pinfunction "1_1") (pintype "passive"))
      (node (ref "U2") (pin "78") (pinfunction "PD7/UART3_RX/SWCLK_78") (pintype "passive"))
    )
    (net (code "43") (name "/SWIO") (class "Default")
      (node (ref "J2") (pin "3") (pinfunction "3_3") (pintype "passive"))
      (node (ref "R15") (pin "2") (pinfunction "2_2") (pintype "passive"))
      (node (ref "U2") (pin "79") (pinfunction "PD8/UART3_TX/SWIO_79") (pintype "passive"))
    )
    (net (code "44") (name "/SWITCH") (class "Default")
      (node (ref "C13") (pin "1") (pinfunction "1_1") (pintype "passive"))
      (node (ref "SW1") (pin "1") (pinfunction "1_1") (pintype "passive"))
      (node (ref "U2") (pin "49") (pinfunction "PC3/XTHOUT/UART1_TX/LPUART1_TX_49") (pintype "passive"))
    )
    (net (code "45") (name "/TXD1") (class "Default")
      (node (ref "U2") (pin "35") (pinfunction "PB14/SEG12/UART1_TX/LPUART1_TX_35") (pintype "passive"))
      (node (ref "U3") (pin "8") (pinfunction "P0.12_8") (pintype "passive"))
    )
    (net (code "46") (name "/TXD4") (class "Default")
      (node (ref "R33") (pin "2") (pinfunction "2_2") (pintype "passive"))
      (node (ref "U2") (pin "24") (pinfunction "PB3/VCIN2/UART4_TX/ATIM_CH2N_24") (pintype "passive"))
    )
    (net (code "47") (name "/USIM_CLK") (class "Default")
      (node (ref "R11") (pin "1") (pinfunction "1_1") (pintype "passive"))
      (node (ref "U4") (pin "13") (pinfunction "UISM1_CLK_13") (pintype "passive"))
    )
    (net (code "48") (name "/USIM_DATA") (class "Default")
      (node (ref "R13") (pin "1") (pinfunction "1_1") (pintype "passive"))
      (node (ref "U4") (pin "11") (pinfunction "USIM1_DATA_11") (pintype "passive"))
    )
    (net (code "49") (name "/USIM_RST") (class "Default")
      (node (ref "R12") (pin "1") (pinfunction "1_1") (pintype "passive"))
      (node (ref "U4") (pin "12") (pinfunction "USIM1_RST_12") (pintype "passive"))
    )
    (net (code "50") (name "/VDD_BLE_CTL") (class "Default")
      (node (ref "R22") (pin "1") (pinfunction "1_1") (pintype "passive"))
      (node (ref "U2") (pin "36") (pinfunction "PE0/SEG36/SPI0_SSN_36") (pintype "passive"))
    )
    (net (code "51") (name "/WY_CTR") (class "Default")
      (node (ref "R29") (pin "1") (pinfunction "1_1") (pintype "passive"))
      (node (ref "U2") (pin "54") (pinfunction "PC8/SEG17/ADC_IN13/SPI2_SCK_54") (pintype "passive"))
    )
    (net (code "52") (name "/WY_SCL") (class "Default")
      (node (ref "J3") (pin "4") (pinfunction "4_4") (pintype "passive"))
      (node (ref "R20") (pin "1") (pinfunction "1_1") (pintype "passive"))
      (node (ref "SCL") (pin "1") (pinfunction "1_1") (pintype "passive"))
      (node (ref "U2") (pin "56") (pinfunction "PC10(WKUP5)/SEG19/ADC_IN15/SPI2_MOSI_56") (pintype "passive"))
      (node (ref "U8") (pin "5") (pinfunction "SCL_5") (pintype "passive"))
    )
    (net (code "53") (name "/WY_SDA") (class "Default")
      (node (ref "J3") (pin "3") (pinfunction "3_3") (pintype "passive"))
      (node (ref "R19") (pin "1") (pinfunction "1_1") (pintype "passive"))
      (node (ref "SDA") (pin "1") (pinfunction "1_1") (pintype "passive"))
      (node (ref "U2") (pin "55") (pinfunction "PC9/SEG18/ADC_IN14/SPI2_MISO_55") (pintype "passive"))
      (node (ref "U8") (pin "6") (pinfunction "SDA_6") (pintype "passive"))
    )
    (net (code "54") (name "/WY_VCC") (class "Default")
      (node (ref "C31") (pin "1") (pinfunction "1_1") (pintype "passive"))
      (node (ref "C43") (pin "1") (pinfunction "1_1") (pintype "passive"))
      (node (ref "C44") (pin "1") (pinfunction "1_1") (pintype "passive"))
      (node (ref "J3") (pin "1") (pinfunction "1_1") (pintype "passive"))
      (node (ref "Q4") (pin "3") (pinfunction "D_3") (pintype "passive"))
      (node (ref "R18") (pin "2") (pinfunction "2_2") (pintype "passive"))
      (node (ref "R19") (pin "2") (pinfunction "2_2") (pintype "passive"))
      (node (ref "R20") (pin "2") (pinfunction "2_2") (pintype "passive"))
      (node (ref "U8") (pin "1") (pinfunction "VDDIO_1") (pintype "passive"))
      (node (ref "U8") (pin "3") (pinfunction "VDD_3") (pintype "passive"))
      (node (ref "WY_V") (pin "1") (pinfunction "1_1") (pintype "passive"))
    )
    (net (code "55") (name "/XT1") (class "Default")
      (node (ref "C14") (pin "2") (pinfunction "2_2") (pintype "passive"))
      (node (ref "U2") (pin "61") (pinfunction "XT32KI_61") (pintype "passive"))
      (node (ref "Y1") (pin "1") (pinfunction "1_1") (pintype "passive"))
    )
    (net (code "56") (name "/XT2") (class "Default")
      (node (ref "C5") (pin "2") (pinfunction "2_2") (pintype "passive"))
      (node (ref "U2") (pin "60") (pinfunction "XT32KO_60") (pintype "passive"))
      (node (ref "Y1") (pin "2") (pinfunction "2_2") (pintype "passive"))
    )
    (net (code "57") (name "3.3V") (class "Default")
      (node (ref "3.3V") (pin "1") (pinfunction "1_1") (pintype "passive"))
      (node (ref "C2") (pin "1") (pinfunction "1_1") (pintype "passive"))
      (node (ref "C22") (pin "2") (pinfunction "2_2") (pintype "passive"))
      (node (ref "C25") (pin "2") (pinfunction "2_2") (pintype "passive"))
      (node (ref "C3") (pin "1") (pinfunction "1_1") (pintype "passive"))
      (node (ref "C4") (pin "1") (pinfunction "1_1") (pintype "passive"))
      (node (ref "C6") (pin "1") (pinfunction "1_1") (pintype "passive"))
      (node (ref "J2") (pin "5") (pinfunction "5_5") (pintype "passive"))
      (node (ref "Q11") (pin "2") (pinfunction "E_2") (pintype "passive"))
      (node (ref "Q4") (pin "2") (pinfunction "S_2") (pintype "passive"))
      (node (ref "Q7") (pin "2") (pinfunction "S_2") (pintype "passive"))
      (node (ref "R10") (pin "2") (pinfunction "2_2") (pintype "passive"))
      (node (ref "R15") (pin "1") (pinfunction "1_1") (pintype "passive"))
      (node (ref "R16") (pin "2") (pinfunction "2_2") (pintype "passive"))
      (node (ref "R17") (pin "2") (pinfunction "2_2") (pintype "passive"))
      (node (ref "R8") (pin "2") (pinfunction "2_2") (pintype "passive"))
      (node (ref "U2") (pin "64") (pinfunction "VDD(VDDA)_64") (pintype "passive"))
      (node (ref "U2") (pin "66") (pinfunction "VREFP_66") (pintype "passive"))
      (node (ref "U2") (pin "67") (pinfunction "VBAT_67") (pintype "passive"))
      (node (ref "U5") (pin "3") (pinfunction "Vout_3") (pintype "passive"))
    )
    (net (code "58") (name "CAT.1_VCC") (class "Default")
      (node (ref "C16") (pin "1") (pinfunction "1_1") (pintype "passive"))
      (node (ref "C17") (pin "1") (pinfunction "1_1") (pintype "passive"))
      (node (ref "C18") (pin "1") (pinfunction "1_1") (pintype "passive"))
      (node (ref "C30") (pin "2") (pinfunction "2_2") (pintype "passive"))
      (node (ref "C33") (pin "1") (pinfunction "1_1") (pintype "passive"))
      (node (ref "Q1") (pin "3") (pinfunction "D_3") (pintype "passive"))
      (node (ref "U4") (pin "42") (pinfunction "VBAT_42") (pintype "passive"))
      (node (ref "U4") (pin "43") (pinfunction "VBAT_43") (pintype "passive"))
      (node (ref "VCAT.1") (pin "1") (pinfunction "1_1") (pintype "passive"))
    )
    (net (code "59") (name "CAT.1_VIN") (class "Default")
      (node (ref "C15") (pin "1") (pinfunction "1_1") (pintype "passive"))
      (node (ref "C21") (pin "1") (pinfunction "1_1") (pintype "passive"))
      (node (ref "C26") (pin "1") (pinfunction "1_1") (pintype "passive"))
      (node (ref "D2") (pin "2") (pinfunction "2_2") (pintype "passive"))
      (node (ref "Q1") (pin "2") (pinfunction "S_2") (pintype "passive"))
      (node (ref "R3") (pin "2") (pinfunction "2_2") (pintype "passive"))
    )
    (net (code "60") (name "EARTH") (class "Default")
      (node (ref "C45") (pin "1") (pinfunction "1_1") (pintype "passive"))
      (node (ref "R80") (pin "2") (pinfunction "2_2") (pintype "passive"))
    )
    (net (code "61") (name "GND") (class "Default")
      (node (ref "C1") (pin "2") (pinfunction "2_2") (pintype "passive"))
      (node (ref "C10") (pin "1") (pinfunction "1_1") (pintype "passive"))
      (node (ref "C11") (pin "1") (pinfunction "1_1") (pintype "passive"))
      (node (ref "C12") (pin "2") (pinfunction "2_2") (pintype "passive"))
      (node (ref "C13") (pin "2") (pinfunction "2_2") (pintype "passive"))
      (node (ref "C14") (pin "1") (pinfunction "1_1") (pintype "passive"))
      (node (ref "C15") (pin "2") (pinfunction "2_2") (pintype "passive"))
      (node (ref "C16") (pin "2") (pinfunction "2_2") (pintype "passive"))
      (node (ref "C17") (pin "2") (pinfunction "2_2") (pintype "passive"))
      (node (ref "C18") (pin "2") (pinfunction "2_2") (pintype "passive"))
      (node (ref "C19") (pin "2") (pinfunction "2_2") (pintype "passive"))
      (node (ref "C2") (pin "2") (pinfunction "2_2") (pintype "passive"))
      (node (ref "C20") (pin "1") (pinfunction "1_1") (pintype "passive"))
      (node (ref "C21") (pin "2") (pinfunction "2_2") (pintype "passive"))
      (node (ref "C22") (pin "1") (pinfunction "1_1") (pintype "passive"))
      (node (ref "C23") (pin "1") (pinfunction "1_1") (pintype "passive"))
      (node (ref "C24") (pin "2") (pinfunction "2_2") (pintype "passive"))
      (node (ref "C25") (pin "1") (pinfunction "1_1") (pintype "passive"))
      (node (ref "C26") (pin "2") (pinfunction "2_2") (pintype "passive"))
      (node (ref "C27") (pin "2") (pinfunction "2_2") (pintype "passive"))
      (node (ref "C28") (pin "2") (pinfunction "2_2") (pintype "passive"))
      (node (ref "C29") (pin "2") (pinfunction "2_2") (pintype "passive"))
      (node (ref "C3") (pin "2") (pinfunction "2_2") (pintype "passive"))
      (node (ref "C30") (pin "1") (pinfunction "1_1") (pintype "passive"))
      (node (ref "C31") (pin "2") (pinfunction "2_2") (pintype "passive"))
      (node (ref "C33") (pin "2") (pinfunction "2_2") (pintype "passive"))
      (node (ref "C34") (pin "1") (pinfunction "1_1") (pintype "passive"))
      (node (ref "C4") (pin "2") (pinfunction "2_2") (pintype "passive"))
      (node (ref "C43") (pin "2") (pinfunction "2_2") (pintype "passive"))
      (node (ref "C44") (pin "2") (pinfunction "2_2") (pintype "passive"))
      (node (ref "C45") (pin "2") (pinfunction "2_2") (pintype "passive"))
      (node (ref "C5") (pin "1") (pinfunction "1_1") (pintype "passive"))
      (node (ref "C6") (pin "2") (pinfunction "2_2") (pintype "passive"))
      (node (ref "C9") (pin "2") (pinfunction "2_2") (pintype "passive"))
      (node (ref "GND") (pin "1") (pinfunction "1_1") (pintype "passive"))
      (node (ref "J1") (pin "1") (pinfunction "1_1") (pintype "passive"))
      (node (ref "J2") (pin "4") (pinfunction "4_4") (pintype "passive"))
      (node (ref "J3") (pin "2") (pinfunction "2_2") (pintype "passive"))
      (node (ref "J3") (pin "5") (pinfunction "5_5") (pintype "passive"))
      (node (ref "J3") (pin "6") (pinfunction "6_6") (pintype "passive"))
      (node (ref "J4") (pin "4") (pinfunction "4_4") (pintype "passive"))
      (node (ref "Q10") (pin "2") (pinfunction "E_2") (pintype "passive"))
      (node (ref "Q6") (pin "2") (pinfunction "E_2") (pintype "passive"))
      (node (ref "Q8") (pin "2") (pinfunction "E_2") (pintype "passive"))
      (node (ref "Q9") (pin "2") (pinfunction "E_2") (pintype "passive"))
      (node (ref "R26") (pin "1") (pinfunction "1_1") (pintype "passive"))
      (node (ref "R28") (pin "2") (pinfunction "2_2") (pintype "passive"))
      (node (ref "R31") (pin "1") (pinfunction "1_1") (pintype "passive"))
      (node (ref "R35") (pin "1") (pinfunction "1_1") (pintype "passive"))
      (node (ref "R41") (pin "2") (pinfunction "2_2") (pintype "passive"))
      (node (ref "R80") (pin "1") (pinfunction "1_1") (pintype "passive"))
      (node (ref "SIM1") (pin "1") (pinfunction "VSS_1") (pintype "passive"))
      (node (ref "SW1") (pin "2") (pinfunction "2_2") (pintype "passive"))
      (node (ref "U2") (pin "63") (pinfunction "VSS(VSSA)_63") (pintype "passive"))
      (node (ref "U2") (pin "65") (pinfunction "VREFN_65") (pintype "passive"))
      (node (ref "U3") (pin "1") (pinfunction "GND_1") (pintype "passive"))
      (node (ref "U3") (pin "15") (pinfunction "GND_15") (pintype "passive"))
      (node (ref "U4") (pin "1") (pinfunction "GND_1") (pintype "passive"))
      (node (ref "U4") (pin "10") (pinfunction "GND_10") (pintype "passive"))
      (node (ref "U4") (pin "27") (pinfunction "GND_27") (pintype "passive"))
      (node (ref "U4") (pin "34") (pinfunction "GND_34") (pintype "passive"))
      (node (ref "U4") (pin "36") (pinfunction "GND_36") (pintype "passive"))
      (node (ref "U4") (pin "37") (pinfunction "GND_37") (pintype "passive"))
      (node (ref "U4") (pin "40") (pinfunction "GND_40") (pintype "passive"))
      (node (ref "U4") (pin "41") (pinfunction "GND_41") (pintype "passive"))
      (node (ref "U4") (pin "45") (pinfunction "GND_45") (pintype "passive"))
      (node (ref "U4") (pin "46") (pinfunction "GND_46") (pintype "passive"))
      (node (ref "U4") (pin "47") (pinfunction "GND_47") (pintype "passive"))
      (node (ref "U4") (pin "48") (pinfunction "GND_48") (pintype "passive"))
      (node (ref "U4") (pin "70") (pinfunction "GND_70") (pintype "passive"))
      (node (ref "U4") (pin "71") (pinfunction "GND_71") (pintype "passive"))
      (node (ref "U4") (pin "72") (pinfunction "GND_72") (pintype "passive"))
      (node (ref "U4") (pin "73") (pinfunction "GND_73") (pintype "passive"))
      (node (ref "U4") (pin "88") (pinfunction "GND_88") (pintype "passive"))
      (node (ref "U4") (pin "89") (pinfunction "GND_89") (pintype "passive"))
      (node (ref "U4") (pin "90") (pinfunction "GND_90") (pintype "passive"))
      (node (ref "U4") (pin "91") (pinfunction "GND_91") (pintype "passive"))
      (node (ref "U4") (pin "92") (pinfunction "GND_92") (pintype "passive"))
      (node (ref "U4") (pin "93") (pinfunction "GND_93") (pintype "passive"))
      (node (ref "U4") (pin "94") (pinfunction "GND_94") (pintype "passive"))
      (node (ref "U4") (pin "95") (pinfunction "GND_95") (pintype "passive"))
      (node (ref "U5") (pin "1") (pinfunction "GND_1") (pintype "passive"))
      (node (ref "U7") (pin "4") (pinfunction "VSS_4") (pintype "passive"))
      (node (ref "U8") (pin "2") (pinfunction "GND_2") (pintype "passive"))
      (node (ref "W1") (pin "2") (pinfunction "GND_2") (pintype "passive"))
    )
    (net (code "62") (name "Net-(J2-Pad1)") (class "Default")
      (node (ref "J2") (pin "1") (pinfunction "1_1") (pintype "passive"))
      (node (ref "R4") (pin "2") (pinfunction "2_2") (pintype "passive"))
    )
    (net (code "63") (name "Net-(J4-Pad1)") (class "Default")
      (node (ref "J4") (pin "1") (pinfunction "1_1") (pintype "passive"))
      (node (ref "R32") (pin "1") (pinfunction "1_1") (pintype "passive"))
    )
    (net (code "64") (name "Net-(J4-Pad2)") (class "Default")
      (node (ref "J4") (pin "2") (pinfunction "2_2") (pintype "passive"))
      (node (ref "R33") (pin "1") (pinfunction "1_1") (pintype "passive"))
    )
    (net (code "65") (name "Net-(J4-Pad3)") (class "Default")
      (node (ref "J4") (pin "3") (pinfunction "3_3") (pintype "passive"))
      (node (ref "R34") (pin "1") (pinfunction "1_1") (pintype "passive"))
    )
    (net (code "66") (name "Net-(Q1-G)") (class "Default")
      (node (ref "Q1") (pin "1") (pinfunction "G_1") (pintype "passive"))
      (node (ref "R3") (pin "1") (pinfunction "1_1") (pintype "passive"))
      (node (ref "R9") (pin "2") (pinfunction "2_2") (pintype "passive"))
    )
    (net (code "67") (name "Net-(Q2-B)") (class "Default")
      (node (ref "C7") (pin "2") (pinfunction "2_2") (pintype "passive"))
      (node (ref "Q2") (pin "1") (pinfunction "B_1") (pintype "passive"))
      (node (ref "R5") (pin "2") (pinfunction "2_2") (pintype "passive"))
    )
    (net (code "68") (name "Net-(Q3-B)") (class "Default")
      (node (ref "C8") (pin "2") (pinfunction "2_2") (pintype "passive"))
      (node (ref "Q3") (pin "1") (pinfunction "B_1") (pintype "passive"))
      (node (ref "R6") (pin "2") (pinfunction "2_2") (pintype "passive"))
    )
    (net (code "69") (name "Net-(Q4-G)") (class "Default")
      (node (ref "Q4") (pin "1") (pinfunction "G_1") (pintype "passive"))
      (node (ref "R17") (pin "1") (pinfunction "1_1") (pintype "passive"))
      (node (ref "R29") (pin "2") (pinfunction "2_2") (pintype "passive"))
    )
    (net (code "70") (name "Net-(Q5-B)") (class "Default")
      (node (ref "Q5") (pin "1") (pinfunction "B_1") (pintype "passive"))
      (node (ref "R25") (pin "2") (pintype "passive"))
    )
    (net (code "71") (name "Net-(Q5-C)") (class "Default")
      (node (ref "Q5") (pin "3") (pinfunction "C_3") (pintype "passive"))
      (node (ref "R24") (pin "2") (pinfunction "2_2") (pintype "passive"))
    )
    (net (code "72") (name "Net-(Q6-B)") (class "Default")
      (node (ref "Q6") (pin "1") (pinfunction "B_1") (pintype "passive"))
      (node (ref "R27") (pin "2") (pintype "passive"))
    )
    (net (code "73") (name "Net-(Q6-C)") (class "Default")
      (node (ref "Q6") (pin "3") (pinfunction "C_3") (pintype "passive"))
      (node (ref "R23") (pin "1") (pintype "passive"))
      (node (ref "R25") (pin "1") (pintype "passive"))
    )
    (net (code "74") (name "Net-(Q7-D)") (class "Default")
      (node (ref "C27") (pin "1") (pinfunction "1_1") (pintype "passive"))
      (node (ref "C28") (pin "1") (pinfunction "1_1") (pintype "passive"))
      (node (ref "Q7") (pin "3") (pinfunction "D_3") (pintype "passive"))
      (node (ref "U3") (pin "14") (pinfunction "VDD_14") (pintype "passive"))
    )
    (net (code "75") (name "Net-(Q7-G)") (class "Default")
      (node (ref "Q7") (pin "1") (pinfunction "G_1") (pintype "passive"))
      (node (ref "R16") (pin "1") (pinfunction "1_1") (pintype "passive"))
      (node (ref "R22") (pin "2") (pinfunction "2_2") (pintype "passive"))
    )
    (net (code "76") (name "Net-(Q8-B)") (class "Default")
      (node (ref "Q8") (pin "1") (pinfunction "B_1") (pintype "passive"))
      (node (ref "R30") (pin "2") (pinfunction "2_2") (pintype "passive"))
      (node (ref "R31") (pin "2") (pinfunction "2_2") (pintype "passive"))
    )
    (net (code "77") (name "Net-(Q9-B)") (class "Default")
      (node (ref "Q9") (pin "1") (pinfunction "B_1") (pintype "passive"))
      (node (ref "R32") (pin "2") (pinfunction "2_2") (pintype "passive"))
      (node (ref "R35") (pin "2") (pinfunction "2_2") (pintype "passive"))
    )
    (net (code "78") (name "Net-(Q10-B)") (class "Default")
      (node (ref "Q10") (pin "1") (pinfunction "B_1") (pintype "passive"))
      (node (ref "R40") (pin "2") (pinfunction "2_2") (pintype "passive"))
      (node (ref "R41") (pin "1") (pinfunction "1_1") (pintype "passive"))
    )
    (net (code "79") (name "Net-(Q11-B)") (class "Default")
      (node (ref "Q11") (pin "1") (pinfunction "B_1") (pintype "passive"))
      (node (ref "R1") (pin "2") (pinfunction "2_2") (pintype "passive"))
    )
    (net (code "80") (name "Net-(Q11-C)") (class "Default")
      (node (ref "C29") (pin "1") (pinfunction "1_1") (pintype "passive"))
      (node (ref "Q11") (pin "3") (pinfunction "C_3") (pintype "passive"))
      (node (ref "U7") (pin "3") (pinfunction "WP#_3") (pintype "passive"))
      (node (ref "U7") (pin "7") (pinfunction "HOLD#_7") (pintype "passive"))
      (node (ref "U7") (pin "8") (pinfunction "VDD_8") (pintype "passive"))
    )
    (net (code "81") (name "Net-(U2-VDD15)") (class "Default")
      (node (ref "C24") (pin "1") (pinfunction "1_1") (pintype "passive"))
      (node (ref "U2") (pin "62") (pinfunction "VDD15_62") (pintype "passive"))
    )
    (net (code "82") (name "Net-(U4A-ANT_MAIN)") (class "Default")
      (node (ref "U4") (pin "35") (pinfunction "ANT_MAIN_35") (pintype "passive"))
      (node (ref "W1") (pin "1") (pinfunction "ANT_1") (pintype "passive"))
    )
    (net (code "83") (name "Net-(U5-Vin)") (class "Default")
      (node (ref "C1") (pin "1") (pinfunction "1_1") (pintype "passive"))
      (node (ref "D1") (pin "2") (pinfunction "2_2") (pintype "passive"))
      (node (ref "U5") (pin "2") (pinfunction "Vin_2") (pintype "passive"))
    )
    (net (code "84") (name "Net-(U8-SDO)") (class "Default")
      (node (ref "R18") (pin "1") (pinfunction "1_1") (pintype "passive"))
      (node (ref "R28") (pin "1") (pinfunction "1_1") (pintype "passive"))
      (node (ref "U8") (pin "8") (pinfunction "SDO_8") (pintype "passive"))
    )
    (net (code "85") (name "SIM_VDD") (class "Default")
      (node (ref "C12") (pin "1") (pinfunction "1_1") (pintype "passive"))
      (node (ref "C9") (pin "1") (pinfunction "1_1") (pintype "passive"))
      (node (ref "SIM1") (pin "8") (pinfunction "VDD_8") (pintype "passive"))
      (node (ref "U4") (pin "14") (pinfunction "USIM1_VDD_14") (pintype "passive"))
    )
    (net (code "86") (name "VDD_EXT") (class "Default")
      (node (ref "C19") (pin "1") (pinfunction "1_1") (pintype "passive"))
      (node (ref "C7") (pin "1") (pinfunction "1_1") (pintype "passive"))
      (node (ref "C8") (pin "1") (pinfunction "1_1") (pintype "passive"))
      (node (ref "R5") (pin "1") (pinfunction "1_1") (pintype "passive"))
      (node (ref "R6") (pin "1") (pinfunction "1_1") (pintype "passive"))
      (node (ref "R7") (pin "2") (pinfunction "2_2") (pintype "passive"))
      (node (ref "U4") (pin "24") (pinfunction "VDD_EXT_24") (pintype "passive"))
    )
    (net (code "87") (name "VIN") (class "Default")
      (node (ref "D1") (pin "1") (pinfunction "1_1") (pintype "passive"))
      (node (ref "D2") (pin "1") (pinfunction "1_1") (pintype "passive"))
      (node (ref "J1") (pin "2") (pinfunction "2_2") (pintype "passive"))
      (node (ref "Q5") (pin "2") (pinfunction "E_2") (pintype "passive"))
      (node (ref "R23") (pin "2") (pintype "passive"))
      (node (ref "VIN") (pin "1") (pinfunction "1_1") (pintype "passive"))
    )
    (net (code "88") (name "unconnected-(SIM1-NC-Pad4)") (class "Default")
      (node (ref "SIM1") (pin "4") (pinfunction "NC_4") (pintype "passive"))
    )
    (net (code "89") (name "unconnected-(SIM1-NC-Pad5)") (class "Default")
      (node (ref "SIM1") (pin "5") (pinfunction "NC_5") (pintype "passive"))
    )
    (net (code "90") (name "unconnected-(U2-PA13{slash}UART0_RX{slash}LPUART0_RX{slash}ADC_IN4-Pad3)") (class "Default")
      (node (ref "U2") (pin "3") (pinfunction "PA13/UART0_RX/LPUART0_RX/ADC_IN4_3") (pintype "passive"))
    )
    (net (code "91") (name "unconnected-(U2-PA14{slash}UART0_TX{slash}LPUART0_TX{slash}ADC_IN11-Pad4)") (class "Default")
      (node (ref "U2") (pin "4") (pinfunction "PA14/UART0_TX/LPUART0_TX/ADC_IN11_4") (pintype "passive"))
    )
    (net (code "92") (name "unconnected-(U2-PA15{slash}WKUP0{slash}SVS{slash}COMP3_OUT-Pad5)") (class "Default")
      (node (ref "U2") (pin "5") (pinfunction "PA15/WKUP0/SVS/COMP3_OUT_5") (pintype "passive"))
    )
    (net (code "93") (name "unconnected-(U2-PB7{slash}SEG6{slash}ATIM_CH4{slash}SPI2_SCK{slash}ANATST-Pad28)") (class "Default")
      (node (ref "U2") (pin "28") (pinfunction "PB7/SEG6/ATIM_CH4/SPI2_SCK/ANATST_28") (pintype "passive"))
    )
    (net (code "94") (name "unconnected-(U2-PB15{slash}VDISP0{slash}SCL1{slash}SPI2_MISO-Pad44)") (class "Default")
      (node (ref "U2") (pin "44") (pinfunction "PB15/VDISP0/SCL1/SPI2_MISO_44") (pintype "passive"))
    )
    (net (code "95") (name "unconnected-(U2-PC0{slash}VDISP2{slash}GPT1_CH1{slash}COMP3_INP1{slash}LUT0_OUT-Pad46)") (class "Default")
      (node (ref "U2") (pin "46") (pinfunction "PC0/VDISP2/GPT1_CH1/COMP3_INP1/LUT0_OUT_46") (pintype "passive"))
    )
    (net (code "96") (name "unconnected-(U2-PC1{slash}VDISP3{slash}GPT1_CH2{slash}COMP3_INP2{slash}LUT1_OUT-Pad47)") (class "Default")
      (node (ref "U2") (pin "47") (pinfunction "PC1/VDISP3/GPT1_CH2/COMP3_INP2/LUT1_OUT_47") (pintype "passive"))
    )
    (net (code "97") (name "unconnected-(U2-PC2{slash}XTHIN{slash}UART1_RX{slash}LPUART1_RX-Pad48)") (class "Default")
      (node (ref "U2") (pin "48") (pinfunction "PC2/XTHIN/UART1_RX/LPUART1_RX_48") (pintype "passive"))
    )
    (net (code "98") (name "unconnected-(U2-PC12{slash}SEG21{slash}U7816IO{slash}GPTO_CH4{slash}ADC_IN17-Pad58)") (class "Default")
      (node (ref "U2") (pin "58") (pinfunction "PC12/SEG21/U7816IO/GPTO_CH4/ADC_IN17_58") (pintype "passive"))
    )
    (net (code "99") (name "unconnected-(U2-PC13{slash}SEG40{slash}U7816CLK{slash}LPT16_CH1-Pad40)") (class "Default")
      (node (ref "U2") (pin "40") (pinfunction "PC13/SEG40/U7816CLK/LPT16_CH1_40") (pintype "passive"))
    )
    (net (code "100") (name "unconnected-(U2-PC14{slash}SEG41{slash}U7816IO{slash}LPT16_CH2-Pad41)") (class "Default")
      (node (ref "U2") (pin "41") (pinfunction "PC14/SEG41/U7816IO/LPT16_CH2_41") (pintype "passive"))
    )
    (net (code "101") (name "unconnected-(U2-PC15{slash}SEG42{slash}LPT32_CH3{slash}CAN_RX-Pad42)") (class "Default")
      (node (ref "U2") (pin "42") (pinfunction "PC15/SEG42/LPT32_CH3/CAN_RX_42") (pintype "passive"))
    )
    (net (code "102") (name "unconnected-(U2-PD0{slash}SEG22{slash}UART5_RX{slash}ADC_IN7{slash}GPT2_CH1-Pad71)") (class "Default")
      (node (ref "U2") (pin "71") (pinfunction "PD0/SEG22/UART5_RX/ADC_IN7/GPT2_CH1_71") (pintype "passive"))
    )
    (net (code "103") (name "unconnected-(U2-PD1{slash}SEG23{slash}UART5_TX{slash}ADC_IN1{slash}GPT2_CH2-Pad72)") (class "Default")
      (node (ref "U2") (pin "72") (pinfunction "PD1/SEG23/UART5_TX/ADC_IN1/GPT2_CH2_72") (pintype "passive"))
    )
    (net (code "104") (name "unconnected-(U2-PD2{slash}SEG24{slash}SPI1_SSN{slash}ADC_IN8{slash}GPT2_CH3-Pad73)") (class "Default")
      (node (ref "U2") (pin "73") (pinfunction "PD2/SEG24/SPI1_SSN/ADC_IN8/GPT2_CH3_73") (pintype "passive"))
    )
    (net (code "105") (name "unconnected-(U2-PD3{slash}SEG25{slash}SPI1_SCK{slash}ADC_IN2{slash}GPT2_CH4-Pad74)") (class "Default")
      (node (ref "U2") (pin "74") (pinfunction "PD3/SEG25/SPI1_SCK/ADC_IN2/GPT2_CH4_74") (pintype "passive"))
    )
    (net (code "106") (name "unconnected-(U2-PD4{slash}SEG26{slash}SPI1_MISO{slash}ADC_IN9{slash}GPT2_ETR-Pad75)") (class "Default")
      (node (ref "U2") (pin "75") (pinfunction "PD4/SEG26/SPI1_MISO/ADC_IN9/GPT2_ETR_75") (pintype "passive"))
    )
    (net (code "107") (name "unconnected-(U2-PD10{slash}CAN_RX{slash}ADC_IN18-Pad1)") (class "Default")
      (node (ref "U2") (pin "1") (pinfunction "PD10/CAN_RX/ADC_IN18_1") (pintype "passive"))
    )
    (net (code "108") (name "unconnected-(U2-PD11(WKUP6){slash}FOUT0{slash}ADC_IN0{slash}ATIM_BRK1-Pad70)") (class "Default")
      (node (ref "U2") (pin "70") (pinfunction "PD11(WKUP6)/FOUT0/ADC_IN0/ATIM_BRK1_70") (pintype "passive"))
    )
    (net (code "109") (name "unconnected-(U2-PD12{slash}VDISP1{slash}SDA1{slash}SPI2_MOSI-Pad45)") (class "Default")
      (node (ref "U2") (pin "45") (pinfunction "PD12/VDISP1/SDA1/SPI2_MOSI_45") (pintype "passive"))
    )
    (net (code "110") (name "unconnected-(U2-PE1{slash}SEG37{slash}SPI0_SCK-Pad37)") (class "Default")
      (node (ref "U2") (pin "37") (pinfunction "PE1/SEG37/SPI0_SCK_37") (pintype "passive"))
    )
    (net (code "111") (name "unconnected-(U2-PE2{slash}SEG38{slash}SPI0_MISO-Pad38)") (class "Default")
      (node (ref "U2") (pin "38") (pinfunction "PE2/SEG38/SPI0_MISO_38") (pintype "passive"))
    )
    (net (code "112") (name "unconnected-(U2-PE3{slash}SEG39{slash}SPI0_MOSI-Pad39)") (class "Default")
      (node (ref "U2") (pin "39") (pinfunction "PE3/SEG39/SPI0_MOSI_39") (pintype "passive"))
    )
    (net (code "113") (name "unconnected-(U2-PE5{slash}SEG43{slash}LPT32_CH4{slash}CAN_TX-Pad43)") (class "Default")
      (node (ref "U2") (pin "43") (pinfunction "PE5/SEG43/LPT32_CH4/CAN_TX_43") (pintype "passive"))
    )
    (net (code "114") (name "unconnected-(U2-PE6(WKUP9)-Pad68)") (class "Default")
      (node (ref "U2") (pin "68") (pinfunction "PE6(WKUP9)_68") (pintype "passive"))
    )
    (net (code "115") (name "unconnected-(U2-PE7{slash}COMP3_OUT-Pad69)") (class "Default")
      (node (ref "U2") (pin "69") (pinfunction "PE7/COMP3_OUT_69") (pintype "passive"))
    )
    (net (code "116") (name "unconnected-(U2-PE8-Pad20)") (class "Default")
      (node (ref "U2") (pin "20") (pinfunction "PE8_20") (pintype "passive"))
    )
    (net (code "117") (name "unconnected-(U2-PE9{slash}CAN_TX{slash}ADC_IN19-Pad2)") (class "Default")
      (node (ref "U2") (pin "2") (pinfunction "PE9/CAN_TX/ADC_IN19_2") (pintype "passive"))
    )
    (net (code "118") (name "unconnected-(U2-PH15{slash}RTCOUT{slash}TAMPER-Pad59)") (class "Default")
      (node (ref "U2") (pin "59") (pinfunction "PH15/RTCOUT/TAMPER_59") (pintype "passive"))
    )
    (net (code "119") (name "unconnected-(U3-P0.00{slash}XL1-Pad13)") (class "Default")
      (node (ref "U3") (pin "13") (pinfunction "P0.00/XL1_13") (pintype "passive"))
    )
    (net (code "120") (name "unconnected-(U3-P0.01{slash}XL2-Pad12)") (class "Default")
      (node (ref "U3") (pin "12") (pinfunction "P0.01/XL2_12") (pintype "passive"))
    )
    (net (code "121") (name "unconnected-(U3-P0.04{slash}AIN2-Pad11)") (class "Default")
      (node (ref "U3") (pin "11") (pinfunction "P0.04/AIN2_11") (pintype "passive"))
    )
    (net (code "122") (name "unconnected-(U3-P0.05{slash}AIN3-Pad10)") (class "Default")
      (node (ref "U3") (pin "10") (pinfunction "P0.05/AIN3_10") (pintype "passive"))
    )
    (net (code "123") (name "unconnected-(U3-P0.16-Pad7)") (class "Default")
      (node (ref "U3") (pin "7") (pinfunction "P0.16_7") (pintype "passive"))
    )
    (net (code "124") (name "unconnected-(U3-P0.18-Pad6)") (class "Default")
      (node (ref "U3") (pin "6") (pinfunction "P0.18_6") (pintype "passive"))
    )
    (net (code "125") (name "unconnected-(U3-P0.20-Pad5)") (class "Default")
      (node (ref "U3") (pin "5") (pinfunction "P0.20_5") (pintype "passive"))
    )
    (net (code "126") (name "unconnected-(U3-SWCLK-Pad3)") (class "Default")
      (node (ref "U3") (pin "3") (pinfunction "SWCLK_3") (pintype "passive"))
    )
    (net (code "127") (name "unconnected-(U3-SWDIO-Pad2)") (class "Default")
      (node (ref "U3") (pin "2") (pinfunction "SWDIO_2") (pintype "passive"))
    )
    (net (code "128") (name "unconnected-(U3-nRESET-Pad4)") (class "Default")
      (node (ref "U3") (pin "4") (pinfunction "nRESET_4") (pintype "passive"))
    )
    (net (code "129") (name "unconnected-(U4A-ADC0-Pad9)") (class "Default")
      (node (ref "U4") (pin "9") (pinfunction "ADC0_9") (pintype "passive"))
    )
    (net (code "130") (name "unconnected-(U4A-ADC1-Pad96)") (class "Default")
      (node (ref "U4") (pin "96") (pinfunction "ADC1_96") (pintype "passive"))
    )
    (net (code "131") (name "unconnected-(U4A-DBG_RXD-Pad38)") (class "Default")
      (node (ref "U4") (pin "38") (pinfunction "DBG_RXD_38") (pintype "passive"))
    )
    (net (code "132") (name "unconnected-(U4A-DBG_TXD-Pad39)") (class "Default")
      (node (ref "U4") (pin "39") (pinfunction "DBG_TXD_39") (pintype "passive"))
    )
    (net (code "133") (name "unconnected-(U4A-MAIN_CTS-Pad22)") (class "Default")
      (node (ref "U4") (pin "22") (pinfunction "MAIN_CTS_22") (pintype "passive"))
    )
    (net (code "134") (name "unconnected-(U4A-MAIN_DCD-Pad21)") (class "Default")
      (node (ref "U4") (pin "21") (pinfunction "MAIN_DCD_21") (pintype "passive"))
    )
    (net (code "135") (name "unconnected-(U4A-MAIN_DTR-Pad19)") (class "Default")
      (node (ref "U4") (pin "19") (pinfunction "MAIN_DTR_19") (pintype "passive"))
    )
    (net (code "136") (name "unconnected-(U4A-MAIN_RI-Pad20)") (class "Default")
      (node (ref "U4") (pin "20") (pinfunction "MAIN_RI_20") (pintype "passive"))
    )
    (net (code "137") (name "unconnected-(U4A-MAIN_RTS-Pad23)") (class "Default")
      (node (ref "U4") (pin "23") (pinfunction "MAIN_RTS_23") (pintype "passive"))
    )
    (net (code "138") (name "unconnected-(U4A-NET_STATUS-Pad16)") (class "Default")
      (node (ref "U4") (pin "16") (pinfunction "NET_STATUS_16") (pintype "passive"))
    )
    (net (code "139") (name "unconnected-(U4A-RESERVED-Pad2)") (class "Default")
      (node (ref "U4") (pin "2") (pinfunction "RESERVED_2") (pintype "passive"))
    )
    (net (code "140") (name "unconnected-(U4A-RESERVED-Pad3)") (class "Default")
      (node (ref "U4") (pin "3") (pinfunction "RESERVED_3") (pintype "passive"))
    )
    (net (code "141") (name "unconnected-(U4A-RESERVED-Pad4)") (class "Default")
      (node (ref "U4") (pin "4") (pinfunction "RESERVED_4") (pintype "passive"))
    )
    (net (code "142") (name "unconnected-(U4A-RESERVED-Pad5)") (class "Default")
      (node (ref "U4") (pin "5") (pinfunction "RESERVED_5") (pintype "passive"))
    )
    (net (code "143") (name "unconnected-(U4A-RESERVED-Pad6)") (class "Default")
      (node (ref "U4") (pin "6") (pinfunction "RESERVED_6") (pintype "passive"))
    )
    (net (code "144") (name "unconnected-(U4A-RESERVED-Pad8)") (class "Default")
      (node (ref "U4") (pin "8") (pinfunction "RESERVED_8") (pintype "passive"))
    )
    (net (code "145") (name "unconnected-(U4A-RESERVED-Pad26)") (class "Default")
      (node (ref "U4") (pin "26") (pinfunction "RESERVED_26") (pintype "passive"))
    )
    (net (code "146") (name "unconnected-(U4A-RESERVED-Pad28)") (class "Default")
      (node (ref "U4") (pin "28") (pinfunction "RESERVED_28") (pintype "passive"))
    )
    (net (code "147") (name "unconnected-(U4A-RESERVED-Pad29)") (class "Default")
      (node (ref "U4") (pin "29") (pinfunction "RESERVED_29") (pintype "passive"))
    )
    (net (code "148") (name "unconnected-(U4A-RESERVED-Pad30)") (class "Default")
      (node (ref "U4") (pin "30") (pinfunction "RESERVED_30") (pintype "passive"))
    )
    (net (code "149") (name "unconnected-(U4A-RESERVED-Pad31)") (class "Default")
      (node (ref "U4") (pin "31") (pinfunction "RESERVED_31") (pintype "passive"))
    )
    (net (code "150") (name "unconnected-(U4A-RESERVED-Pad32)") (class "Default")
      (node (ref "U4") (pin "32") (pinfunction "RESERVED_32") (pintype "passive"))
    )
    (net (code "151") (name "unconnected-(U4A-RESERVED-Pad33)") (class "Default")
      (node (ref "U4") (pin "33") (pinfunction "RESERVED_33") (pintype "passive"))
    )
    (net (code "152") (name "unconnected-(U4A-RESERVED-Pad44)") (class "Default")
      (node (ref "U4") (pin "44") (pinfunction "RESERVED_44") (pintype "passive"))
    )
    (net (code "153") (name "unconnected-(U4A-RESERVED-Pad97)") (class "Default")
      (node (ref "U4") (pin "97") (pinfunction "RESERVED_97") (pintype "passive"))
    )
    (net (code "154") (name "unconnected-(U4A-RESERVED-Pad98)") (class "Default")
      (node (ref "U4") (pin "98") (pinfunction "RESERVED_98") (pintype "passive"))
    )
    (net (code "155") (name "unconnected-(U4A-STATUS-Pad25)") (class "Default")
      (node (ref "U4") (pin "25") (pinfunction "STATUS_25") (pintype "passive"))
    )
    (net (code "156") (name "unconnected-(U4B-I2C_SCL-Pad67)") (class "Default")
      (node (ref "U4") (pin "67") (pinfunction "I2C_SCL_67") (pintype "passive"))
    )
    (net (code "157") (name "unconnected-(U4B-I2C_SDA-Pad66)") (class "Default")
      (node (ref "U4") (pin "66") (pinfunction "I2C_SDA_66") (pintype "passive"))
    )
    (net (code "158") (name "unconnected-(U4B-RESERVED-Pad49)") (class "Default")
      (node (ref "U4") (pin "49") (pinfunction "RESERVED_49") (pintype "passive"))
    )
    (net (code "159") (name "unconnected-(U4B-RESERVED-Pad50)") (class "Default")
      (node (ref "U4") (pin "50") (pinfunction "RESERVED_50") (pintype "passive"))
    )
    (net (code "160") (name "unconnected-(U4B-RESERVED-Pad51)") (class "Default")
      (node (ref "U4") (pin "51") (pinfunction "RESERVED_51") (pintype "passive"))
    )
    (net (code "161") (name "unconnected-(U4B-RESERVED-Pad52)") (class "Default")
      (node (ref "U4") (pin "52") (pinfunction "RESERVED_52") (pintype "passive"))
    )
    (net (code "162") (name "unconnected-(U4B-RESERVED-Pad53)") (class "Default")
      (node (ref "U4") (pin "53") (pinfunction "RESERVED_53") (pintype "passive"))
    )
    (net (code "163") (name "unconnected-(U4B-RESERVED-Pad54)") (class "Default")
      (node (ref "U4") (pin "54") (pinfunction "RESERVED_54") (pintype "passive"))
    )
    (net (code "164") (name "unconnected-(U4B-RESERVED-Pad55)") (class "Default")
      (node (ref "U4") (pin "55") (pinfunction "RESERVED_55") (pintype "passive"))
    )
    (net (code "165") (name "unconnected-(U4B-RESERVED-Pad56)") (class "Default")
      (node (ref "U4") (pin "56") (pinfunction "RESERVED_56") (pintype "passive"))
    )
    (net (code "166") (name "unconnected-(U4B-RESERVED-Pad57)") (class "Default")
      (node (ref "U4") (pin "57") (pinfunction "RESERVED_57") (pintype "passive"))
    )
    (net (code "167") (name "unconnected-(U4B-RESERVED-Pad58)") (class "Default")
      (node (ref "U4") (pin "58") (pinfunction "RESERVED_58") (pintype "passive"))
    )
    (net (code "168") (name "unconnected-(U4B-RESERVED-Pad68)") (class "Default")
      (node (ref "U4") (pin "68") (pinfunction "RESERVED_68") (pintype "passive"))
    )
    (net (code "169") (name "unconnected-(U4B-RESERVED-Pad69)") (class "Default")
      (node (ref "U4") (pin "69") (pinfunction "RESERVED_69") (pintype "passive"))
    )
    (net (code "170") (name "unconnected-(U4B-RESERVED-Pad99)") (class "Default")
      (node (ref "U4") (pin "99") (pinfunction "RESERVED_99") (pintype "passive"))
    )
    (net (code "171") (name "unconnected-(U4B-RESERVED-Pad100)") (class "Default")
      (node (ref "U4") (pin "100") (pinfunction "RESERVED_100") (pintype "passive"))
    )
    (net (code "172") (name "unconnected-(U4B-RESERVED-Pad101)") (class "Default")
      (node (ref "U4") (pin "101") (pinfunction "RESERVED_101") (pintype "passive"))
    )
    (net (code "173") (name "unconnected-(U4B-RESERVED-Pad102)") (class "Default")
      (node (ref "U4") (pin "102") (pinfunction "RESERVED_102") (pintype "passive"))
    )
    (net (code "174") (name "unconnected-(U4B-RESERVED-Pad103)") (class "Default")
      (node (ref "U4") (pin "103") (pinfunction "RESERVED_103") (pintype "passive"))
    )
    (net (code "175") (name "unconnected-(U4B-RESERVED-Pad104)") (class "Default")
      (node (ref "U4") (pin "104") (pinfunction "RESERVED_104") (pintype "passive"))
    )
    (net (code "176") (name "unconnected-(U4B-RESERVED-Pad105)") (class "Default")
      (node (ref "U4") (pin "105") (pinfunction "RESERVED_105") (pintype "passive"))
    )
    (net (code "177") (name "unconnected-(U4B-RESERVED-Pad106)") (class "Default")
      (node (ref "U4") (pin "106") (pinfunction "RESERVED_106") (pintype "passive"))
    )
    (net (code "178") (name "unconnected-(U4B-USB_DM-Pad60)") (class "Default")
      (node (ref "U4") (pin "60") (pinfunction "USB_DM_60") (pintype "passive"))
    )
    (net (code "179") (name "unconnected-(U4B-USB_DP-Pad59)") (class "Default")
      (node (ref "U4") (pin "59") (pinfunction "USB_DP_59") (pintype "passive"))
    )
    (net (code "180") (name "unconnected-(U4B-USB_VBUS-Pad61)") (class "Default")
      (node (ref "U4") (pin "61") (pinfunction "USB_VBUS_61") (pintype "passive"))
    )
    (net (code "181") (name "unconnected-(U4B-USIM2_CLK-Pad62)") (class "Default")
      (node (ref "U4") (pin "62") (pinfunction "USIM2_CLK_62") (pintype "passive"))
    )
    (net (code "182") (name "unconnected-(U4B-USIM2_DATA-Pad64)") (class "Default")
      (node (ref "U4") (pin "64") (pinfunction "USIM2_DATA_64") (pintype "passive"))
    )
    (net (code "183") (name "unconnected-(U4B-USIM2_RST-Pad63)") (class "Default")
      (node (ref "U4") (pin "63") (pinfunction "USIM2_RST_63") (pintype "passive"))
    )
    (net (code "184") (name "unconnected-(U4B-USIM2_VDD-Pad65)") (class "Default")
      (node (ref "U4") (pin "65") (pinfunction "USIM2_VDD_65") (pintype "passive"))
    )
    (net (code "185") (name "unconnected-(U4C-RESERVED-Pad74)") (class "Default")
      (node (ref "U4") (pin "74") (pinfunction "RESERVED_74") (pintype "passive"))
    )
    (net (code "186") (name "unconnected-(U4C-RESERVED-Pad75)") (class "Default")
      (node (ref "U4") (pin "75") (pinfunction "RESERVED_75") (pintype "passive"))
    )
    (net (code "187") (name "unconnected-(U4C-RESERVED-Pad76)") (class "Default")
      (node (ref "U4") (pin "76") (pinfunction "RESERVED_76") (pintype "passive"))
    )
    (net (code "188") (name "unconnected-(U4C-RESERVED-Pad77)") (class "Default")
      (node (ref "U4") (pin "77") (pinfunction "RESERVED_77") (pintype "passive"))
    )
    (net (code "189") (name "unconnected-(U4C-RESERVED-Pad78)") (class "Default")
      (node (ref "U4") (pin "78") (pinfunction "RESERVED_78") (pintype "passive"))
    )
    (net (code "190") (name "unconnected-(U4C-RESERVED-Pad80)") (class "Default")
      (node (ref "U4") (pin "80") (pinfunction "RESERVED_80") (pintype "passive"))
    )
    (net (code "191") (name "unconnected-(U4C-RESERVED-Pad81)") (class "Default")
      (node (ref "U4") (pin "81") (pinfunction "RESERVED_81") (pintype "passive"))
    )
    (net (code "192") (name "unconnected-(U4C-RESERVED-Pad83)") (class "Default")
      (node (ref "U4") (pin "83") (pinfunction "RESERVED_83") (pintype "passive"))
    )
    (net (code "193") (name "unconnected-(U4C-RESERVED-Pad84)") (class "Default")
      (node (ref "U4") (pin "84") (pinfunction "RESERVED_84") (pintype "passive"))
    )
    (net (code "194") (name "unconnected-(U4C-RESERVED-Pad85)") (class "Default")
      (node (ref "U4") (pin "85") (pinfunction "RESERVED_85") (pintype "passive"))
    )
    (net (code "195") (name "unconnected-(U4C-RESERVED-Pad86)") (class "Default")
      (node (ref "U4") (pin "86") (pinfunction "RESERVED_86") (pintype "passive"))
    )
    (net (code "196") (name "unconnected-(U4C-RESERVED-Pad87)") (class "Default")
      (node (ref "U4") (pin "87") (pinfunction "RESERVED_87") (pintype "passive"))
    )
    (net (code "197") (name "unconnected-(U4C-RESERVED-Pad107)") (class "Default")
      (node (ref "U4") (pin "107") (pinfunction "RESERVED_107") (pintype "passive"))
    )
    (net (code "198") (name "unconnected-(U4C-RESERVED-Pad108)") (class "Default")
      (node (ref "U4") (pin "108") (pinfunction "RESERVED_108") (pintype "passive"))
    )
    (net (code "199") (name "unconnected-(U4C-RESERVED-Pad109)") (class "Default")
      (node (ref "U4") (pin "109") (pinfunction "RESERVED_109") (pintype "passive"))
    )
    (net (code "200") (name "unconnected-(U4C-USB_BOOT-Pad82)") (class "Default")
      (node (ref "U4") (pin "82") (pinfunction "USB_BOOT_82") (pintype "passive"))
    )
    (net (code "201") (name "unconnected-(U4C-USIM1_DET-Pad79)") (class "Default")
      (node (ref "U4") (pin "79") (pinfunction "USIM1_DET_79") (pintype "passive"))
    )
    (net (code "202") (name "unconnected-(U8-CSB-Pad7)") (class "Default")
      (node (ref "U8") (pin "7") (pinfunction "CSB_7") (pintype "passive"))
    )
    (net (code "203") (name "unconnected-(U8-NC-Pad4)") (class "Default")
      (node (ref "U8") (pin "4") (pinfunction "NC_4") (pintype "passive+no_connect"))
    )
  )
)
